# Pipa_PRM.net
KiCad netlist of a schematic drawn in Altium Designer
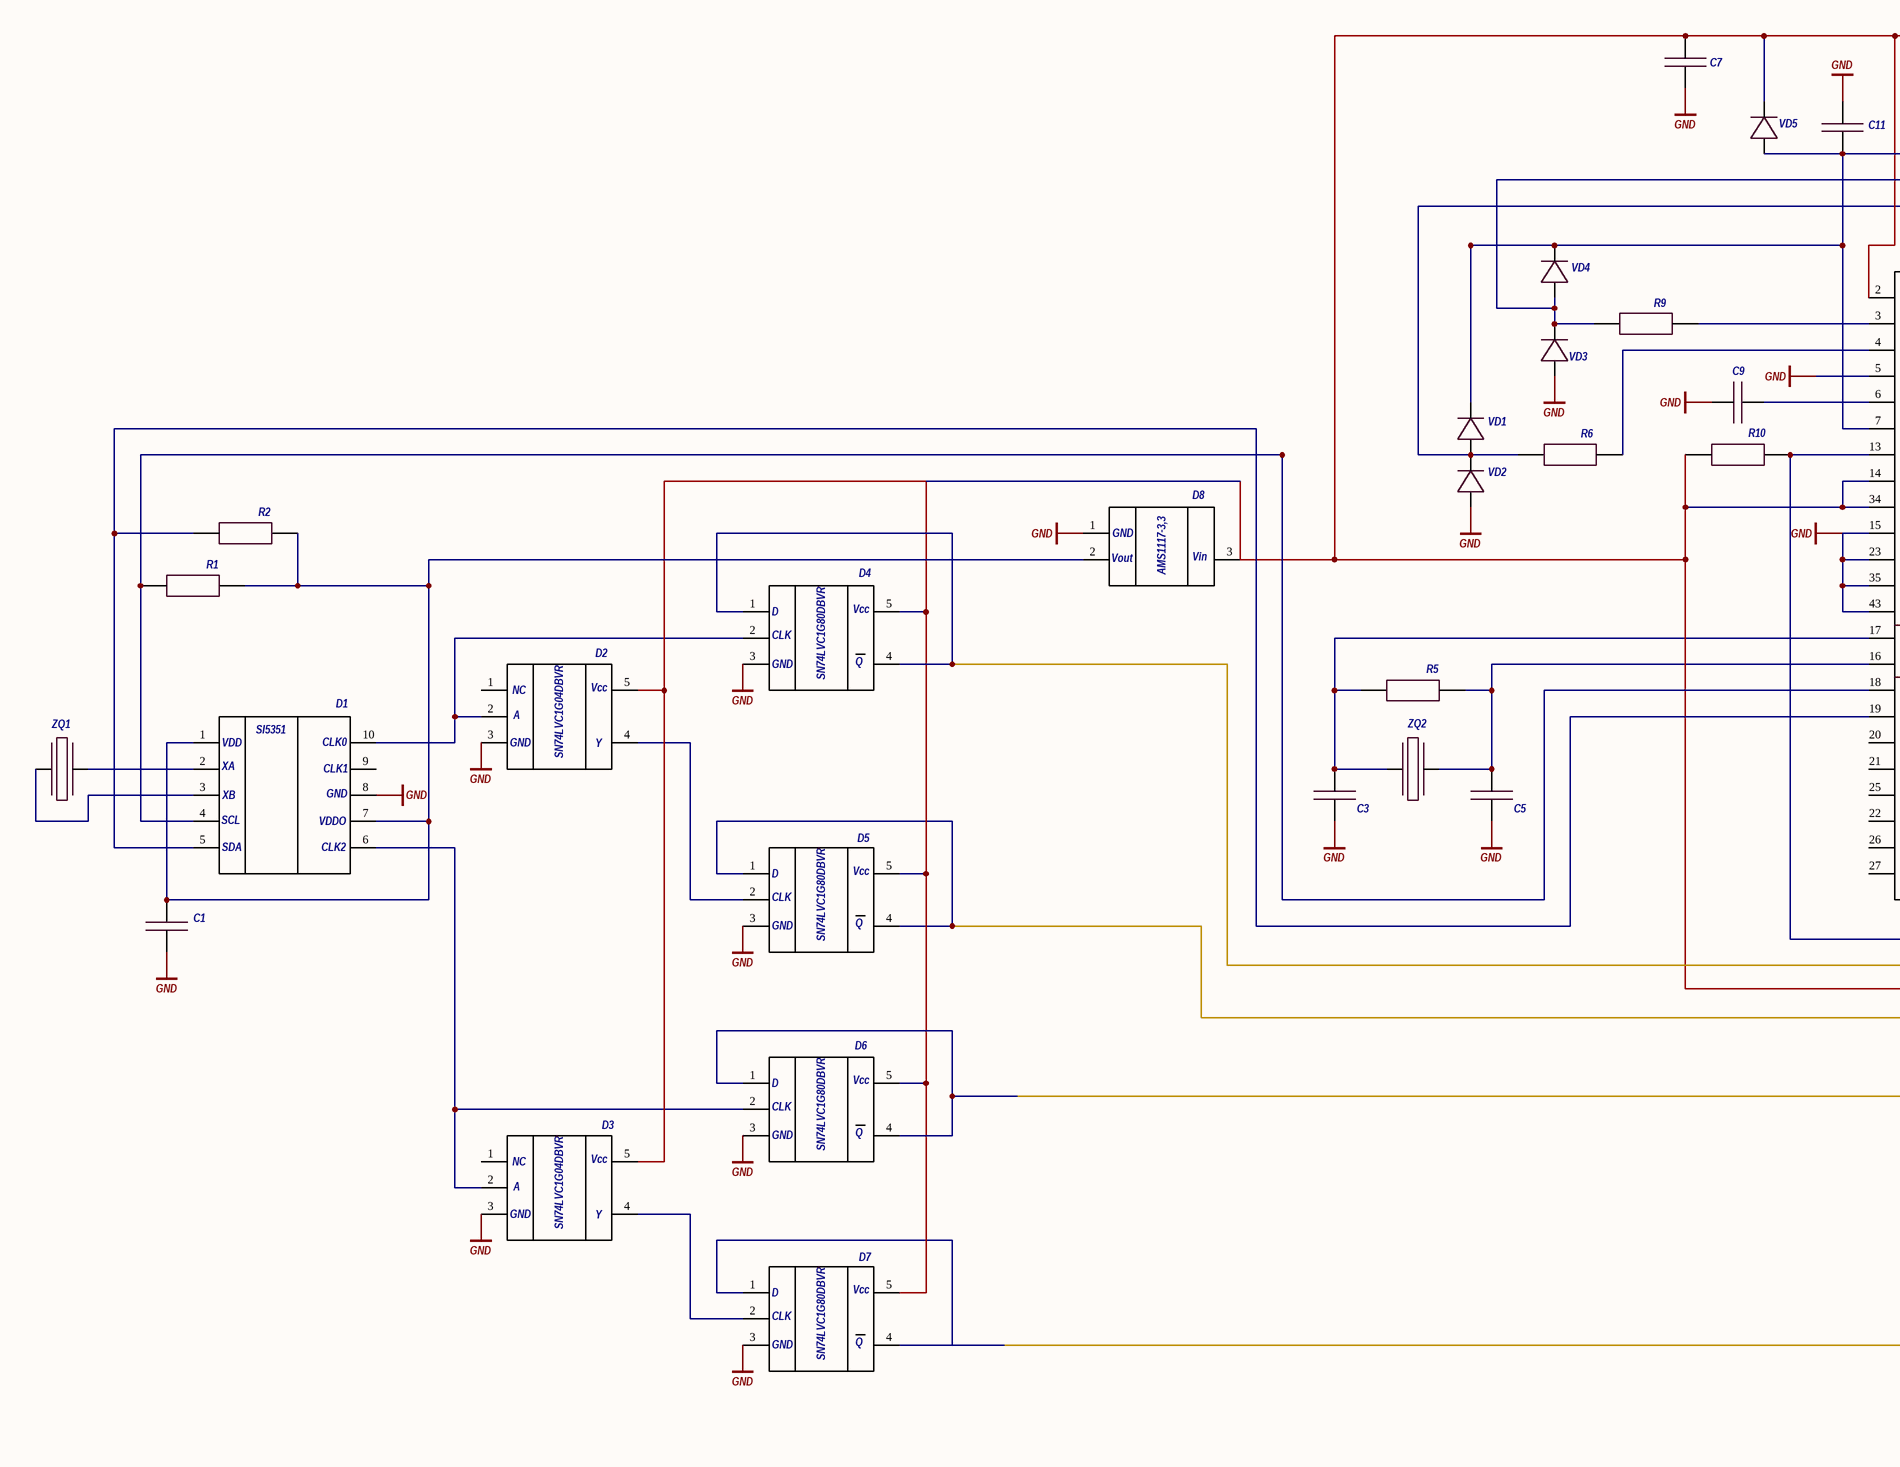
[diagram p0: Pipa PRM.SchDoc, top left]
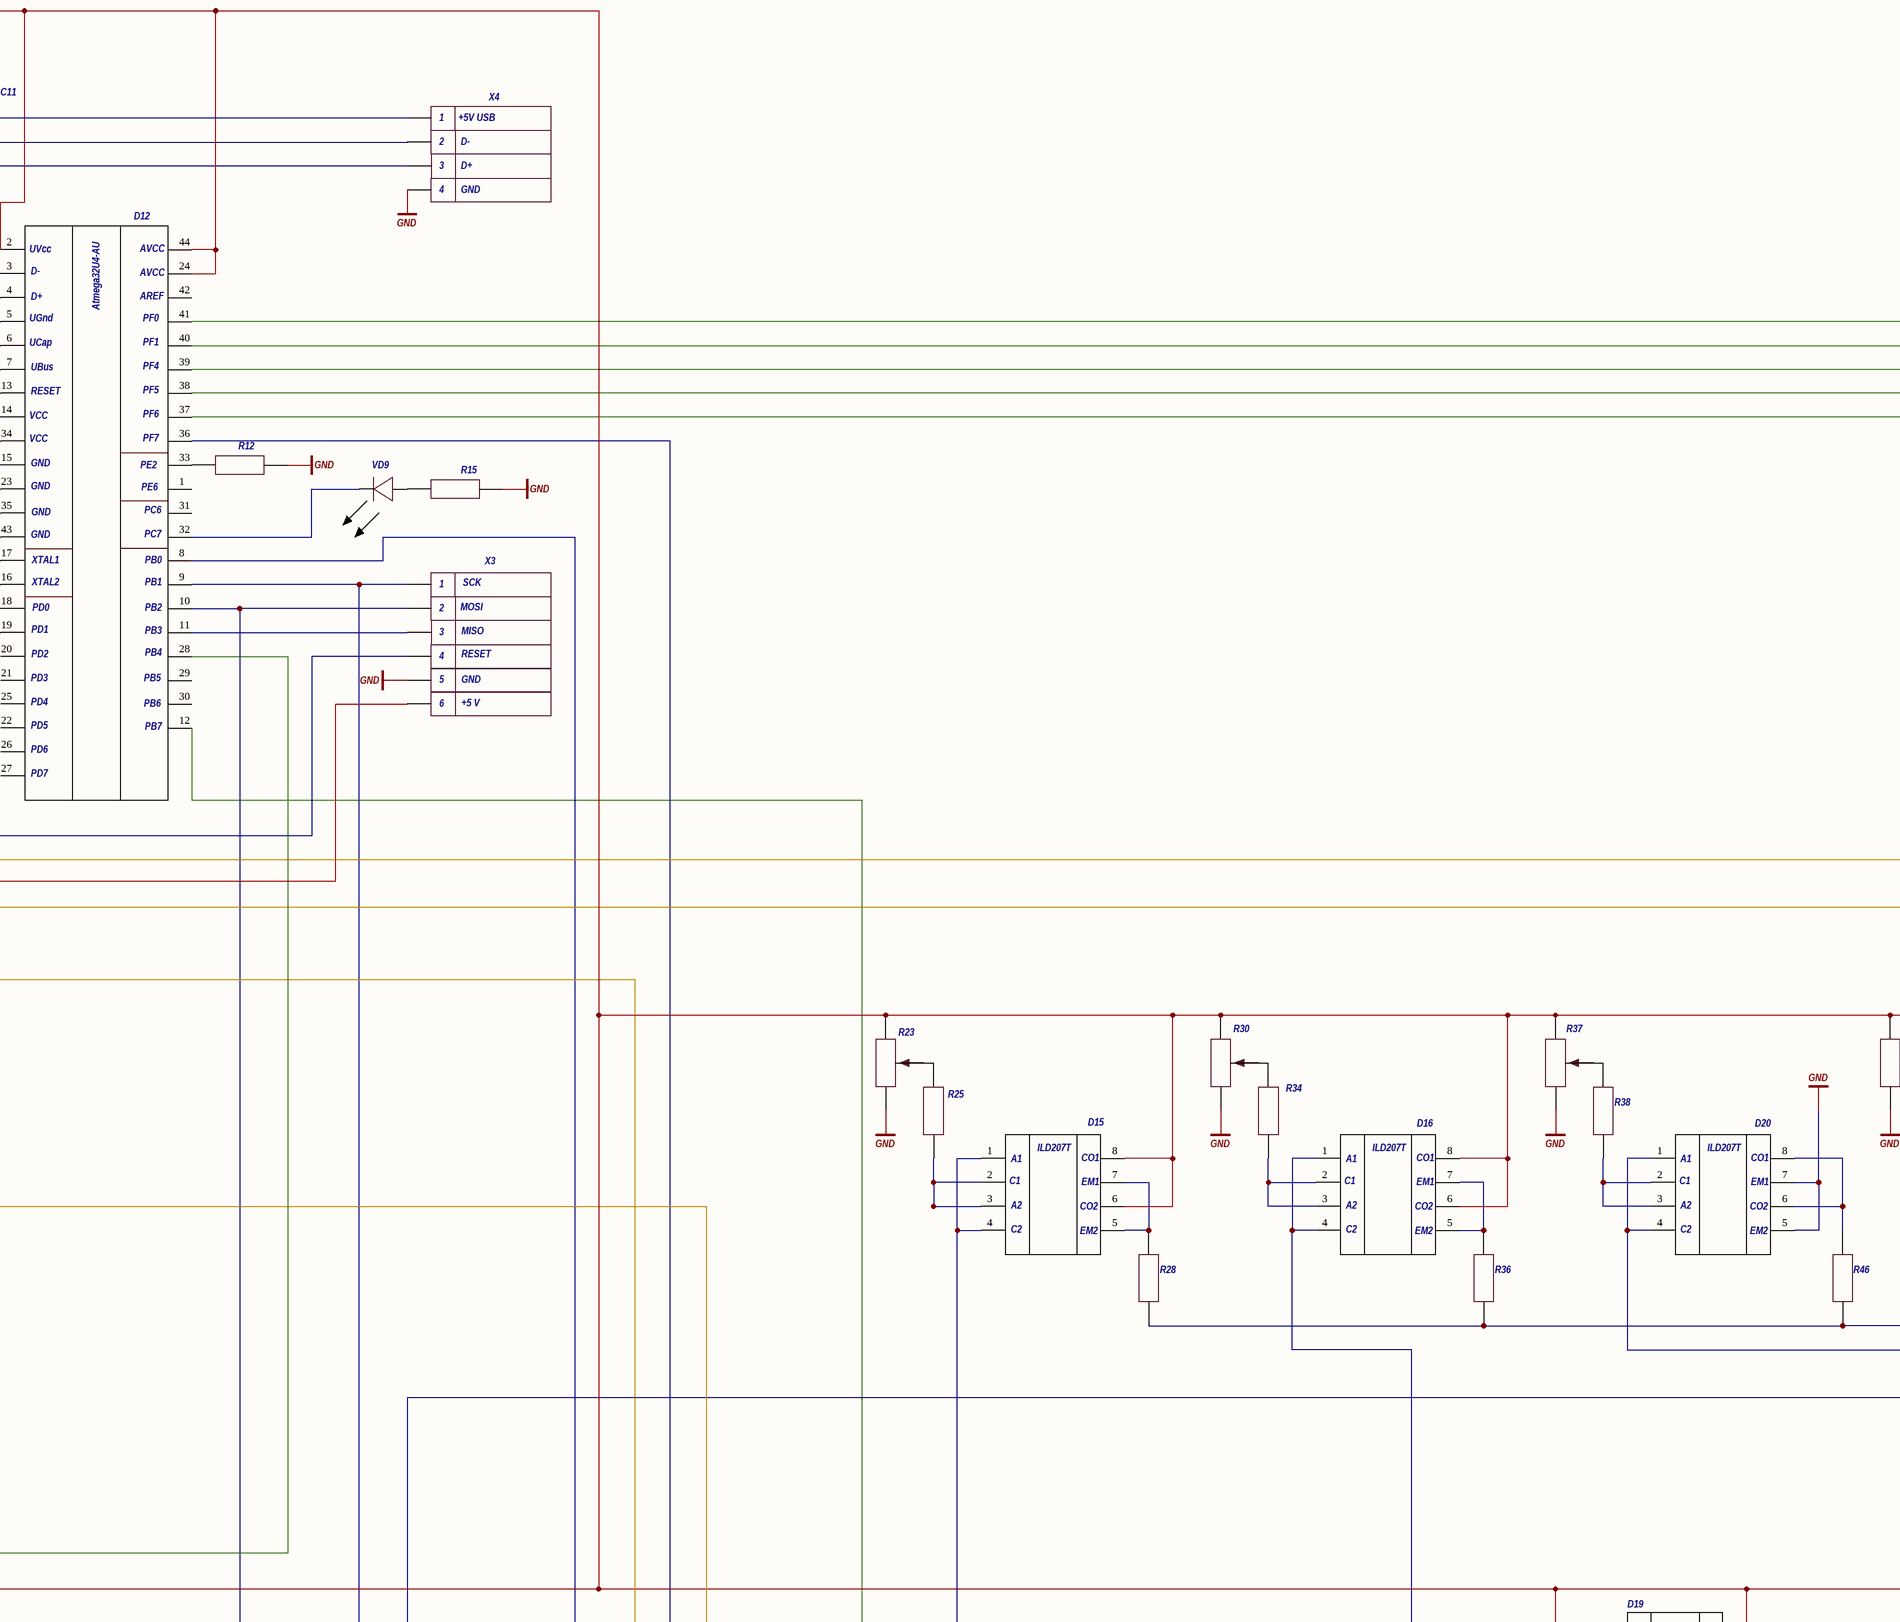
[diagram p1: Pipa PRM.SchDoc, top middle]
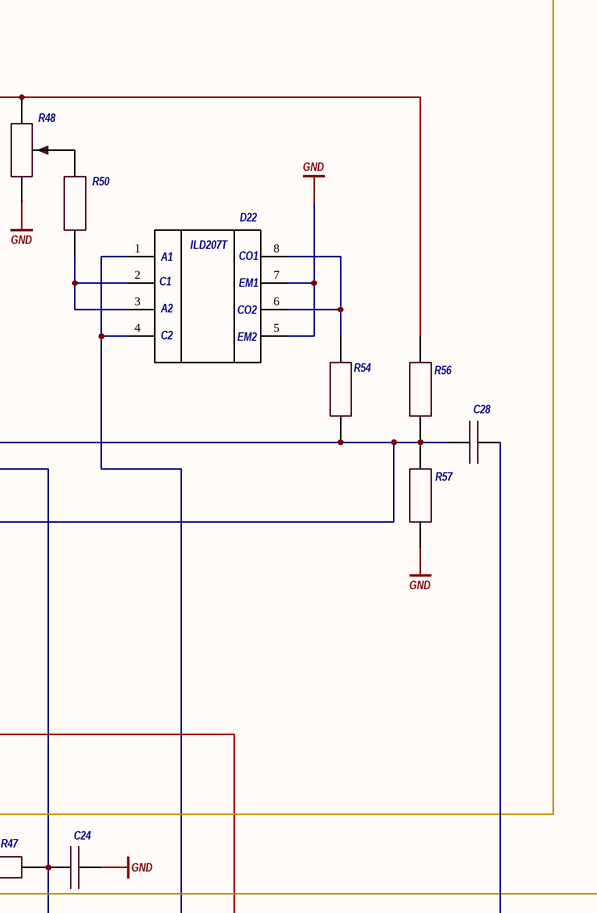
[diagram p2: Pipa PRM.SchDoc, top right]
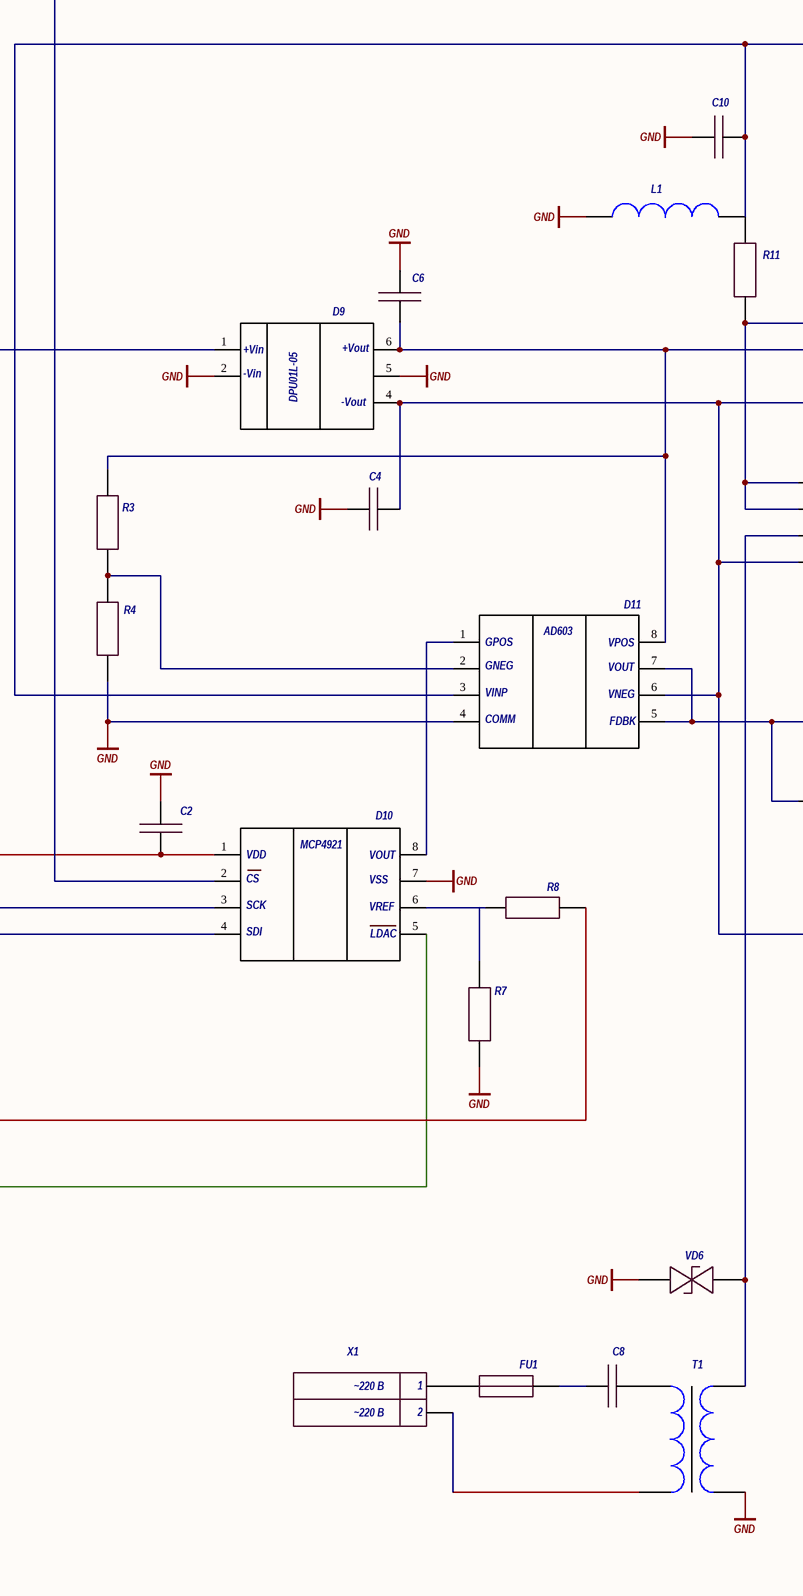
[diagram p3: Pipa PRM.SchDoc, bottom left]
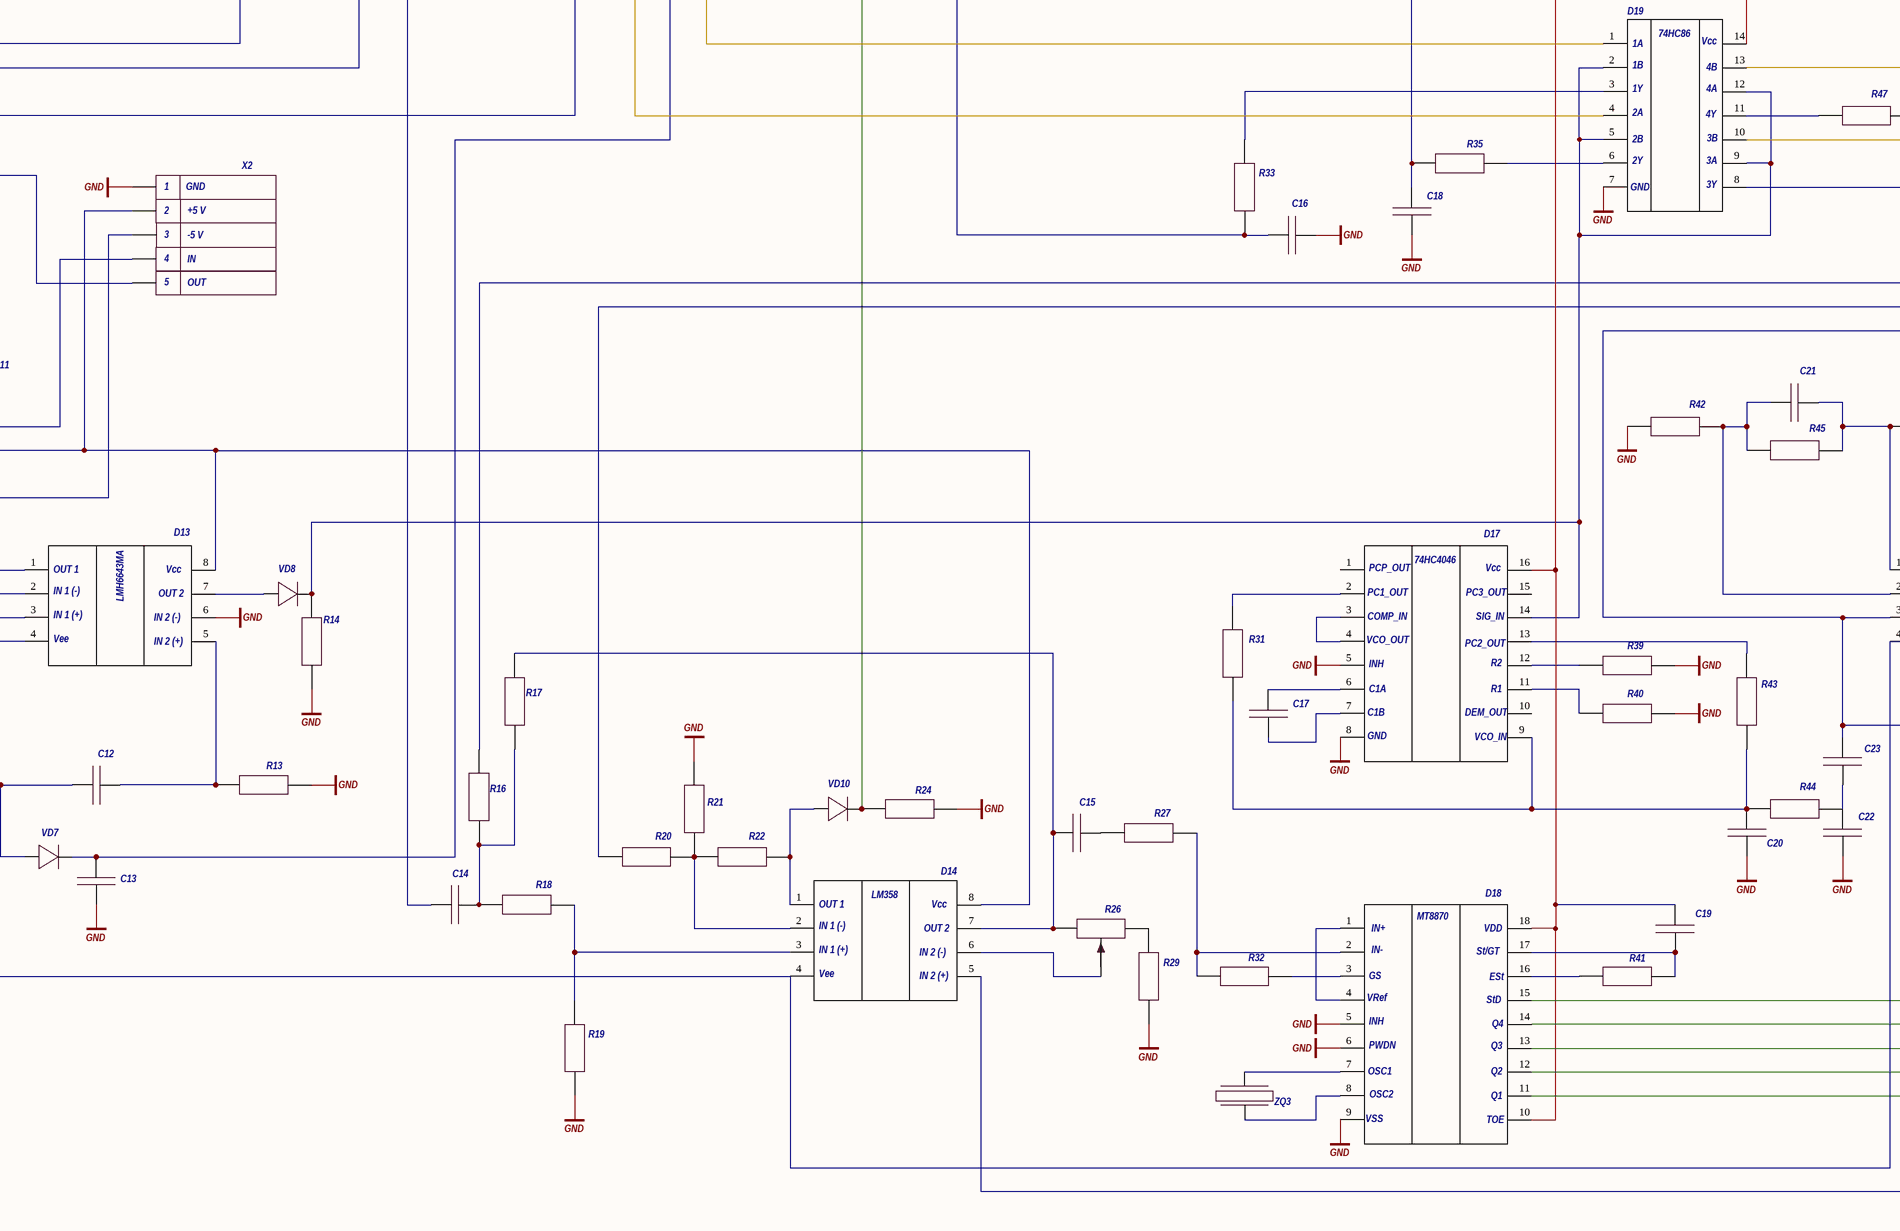
[diagram p4: Pipa PRM.SchDoc, bottom middle]
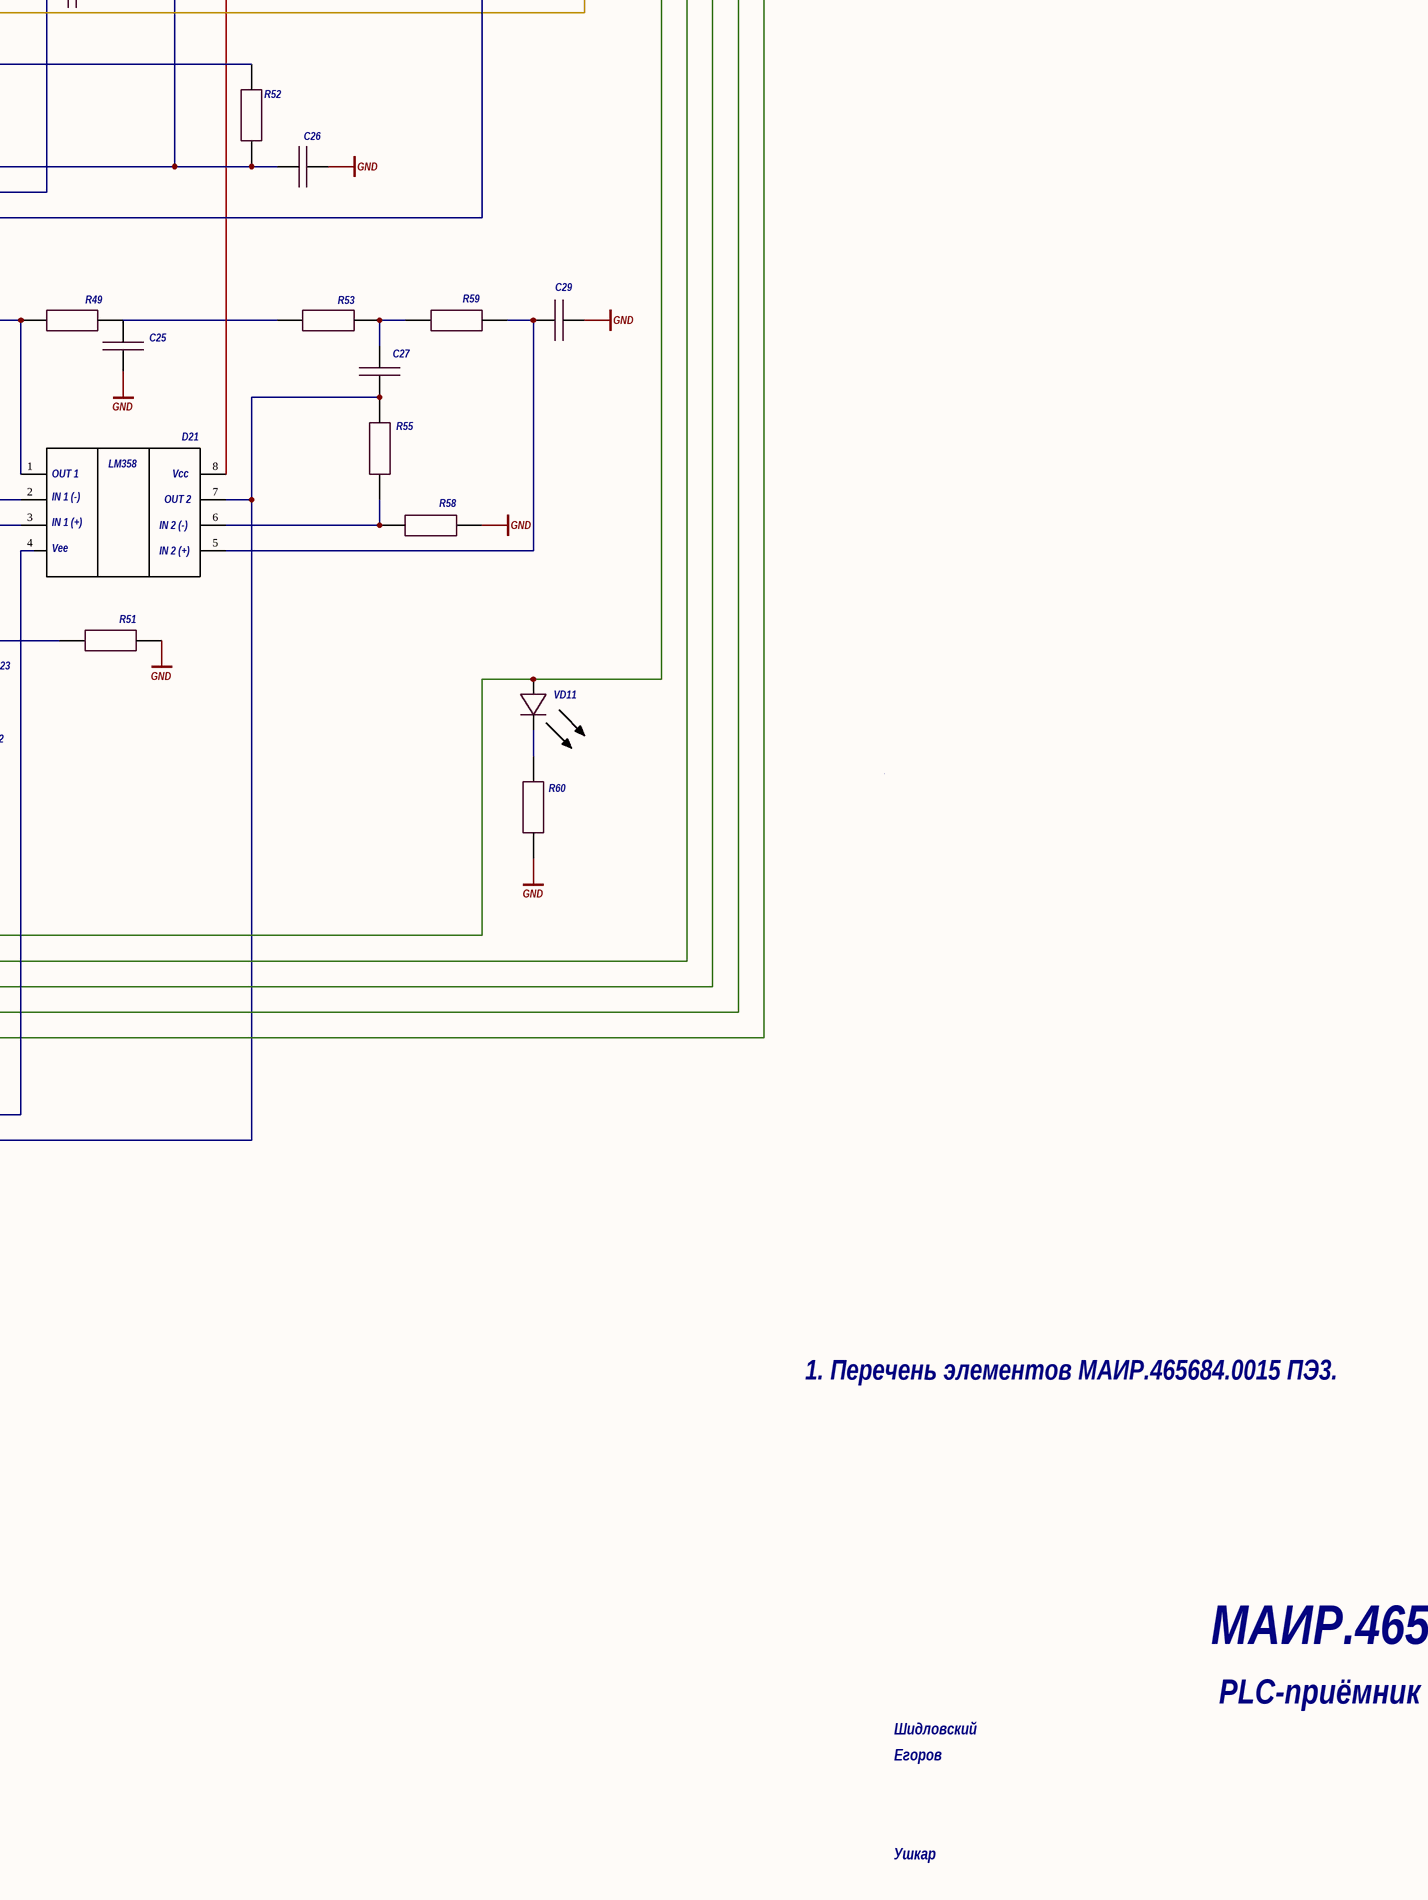
[diagram p5: Pipa PRM.SchDoc, bottom right]

(export (version "E")
  (design (tool "Eeschema 10.0.6"))
  (components
    (comp (ref "C1")
      (value "22 мкФ")
      (footprint "Chokochillipcb:С_0805")
      (libsource (lib "diplom_schlib") (part "Конденсатор"))
    )
    (comp (ref "C2") (value "4,7 мкФ") (libsource (lib "Chokochillisch") (part "Конденсатор")))
    (comp (ref "C3") (value "24 пФ") (libsource (lib "Chokochillisch") (part "Конденсатор")))
    (comp (ref "C4") (value "22 мкФ") (libsource (lib "Chokochillisch") (part "Конденсатор")))
    (comp (ref "C5") (value "24 пФ") (libsource (lib "Chokochillisch") (part "Конденсатор")))
    (comp (ref "C6") (value "22 мкФ") (libsource (lib "Chokochillisch") (part "Конденсатор")))
    (comp (ref "C7")
      (value "470 мкФ 6,3 В Электролит.")
      (libsource (lib "Chokochillisch") (part "Конденсатор"))
    )
    (comp (ref "C8")
      (value "Конденсатор")
      (footprint "Chokochillipcb:С_0805")
      (libsource (lib "diplom_schlib") (part "Конденсатор"))
    )
    (comp (ref "C9") (value "1 мкФ") (libsource (lib "Chokochillisch") (part "Конденсатор")))
    (comp (ref "C10") (value "Конденсатор") (libsource (lib "Chokochillisch") (part "Конденсатор")))
    (comp (ref "C11") (value "10 мкФ") (libsource (lib "Chokochillisch") (part "Конденсатор")))
    (comp (ref "C12") (value "10 мкФ") (libsource (lib "Chokochillisch") (part "Конденсатор")))
    (comp (ref "C13") (value "1 мкФ") (libsource (lib "Chokochillisch") (part "Конденсатор")))
    (comp (ref "C14") (value "22 мкФ") (libsource (lib "Chokochillisch") (part "Конденсатор")))
    (comp (ref "C15")
      (value "1 мкФ")
      (footprint "Chokochillipcb:С_0805")
      (libsource (lib "diplom_schlib") (part "Конденсатор"))
    )
    (comp (ref "C16") (value "100 мкФ (1206)") (libsource (lib "Chokochillisch") (part "Конденсатор")))
    (comp (ref "C17")
      (value "Конденсатор")
      (footprint "Chokochillipcb:С_0805")
      (libsource (lib "diplom_schlib") (part "Конденсатор"))
    )
    (comp (ref "C18") (value "100 мкФ (1206)") (libsource (lib "Chokochillisch") (part "Конденсатор")))
    (comp (ref "C19")
      (value "0,01 мкФ")
      (footprint "Chokochillipcb:С_0805")
      (libsource (lib "diplom_schlib") (part "Конденсатор"))
    )
    (comp (ref "C20")
      (value "Конденсатор")
      (footprint "Chokochillipcb:C_1206")
      (libsource (lib "diplom_schlib") (part "Конденсатор"))
    )
    (comp (ref "C21")
      (value "Конденсатор")
      (footprint "Chokochillipcb:С_0805")
      (libsource (lib "diplom_schlib") (part "Конденсатор"))
    )
    (comp (ref "C22")
      (value "Конденсатор")
      (footprint "Chokochillipcb:С_0805")
      (libsource (lib "diplom_schlib") (part "Конденсатор"))
    )
    (comp (ref "C23") (value "22 мкФ") (libsource (lib "Chokochillisch") (part "Конденсатор")))
    (comp (ref "C24") (value "100 мкФ (1206)") (libsource (lib "Chokochillisch") (part "Конденсатор")))
    (comp (ref "C25") (value "4,3 нФ") (libsource (lib "Chokochillisch") (part "Конденсатор")))
    (comp (ref "C26") (value "100 мкФ (1206)") (libsource (lib "Chokochillisch") (part "Конденсатор")))
    (comp (ref "C27") (value "11 нФ") (libsource (lib "Chokochillisch") (part "Конденсатор")))
    (comp (ref "C28") (value "22 мкФ") (libsource (lib "Chokochillisch") (part "Конденсатор")))
    (comp (ref "C29") (value "620 пФ") (libsource (lib "Chokochillisch") (part "Конденсатор")))
    (comp (ref "D1")
      (value "Микросхема SI5351")
      (footprint "Chokochillipcb:MSOP-10")
      (libsource (lib "diplom_schlib") (part "Микросхема SI5351"))
    )
    (comp (ref "D2")
      (value "Микросхема SN74LVC1G04DBVR")
      (libsource (lib "Chokochillisch") (part "Микросхема SN74LVC1G04DBVR"))
    )
    (comp (ref "D3")
      (value "Микросхема SN74LVC1G04DBVR")
      (libsource (lib "Chokochillisch") (part "Микросхема SN74LVC1G04DBVR"))
    )
    (comp (ref "D4")
      (value "Микросхема SN74LVC1G80DBVR")
      (libsource (lib "Chokochillisch") (part "Микросхема SN74LVC1G80DBVR"))
    )
    (comp (ref "D5")
      (value "Микросхема SN74LVC1G80DBVR")
      (libsource (lib "Chokochillisch") (part "Микросхема SN74LVC1G80DBVR"))
    )
    (comp (ref "D6")
      (value "Микросхема SN74LVC1G80DBVR")
      (libsource (lib "Chokochillisch") (part "Микросхема SN74LVC1G80DBVR"))
    )
    (comp (ref "D7")
      (value "Микросхема SN74LVC1G80DBVR")
      (libsource (lib "Chokochillisch") (part "Микросхема SN74LVC1G80DBVR"))
    )
    (comp (ref "D8")
      (value "Микросхема AMS1117-3,3")
      (footprint "Chokochillipcb:SOT-223")
      (libsource (lib "diplom_schlib") (part "Микросхема AMS1117-3,3"))
    )
    (comp (ref "D9")
      (value "Микросхема DPU01L-05")
      (libsource (lib "Chokochillisch") (part "Микросхема DPU01L-05"))
    )
    (comp (ref "D10")
      (value "Микросхема MCP4921")
      (libsource (lib "Chokochillisch") (part "Микросхема MCP4921"))
    )
    (comp (ref "D11") (value "Микросхема AD603") (libsource (lib "Chokochillisch") (part "Микросхема AD603")))
    (comp (ref "D12")
      (value "Микросхема ATmega32U4-AU")
      (libsource (lib "Chokochillisch") (part "Микросхема ATmega32U4-AU"))
    )
    (comp (ref "D13")
      (value "Микросхема LMH6643MA")
      (libsource (lib "Chokochillisch") (part "Микросхема LMH6643MA"))
    )
    (comp (ref "D14")
      (value "D")
      (footprint "Chokochillipcb:SOP-8")
      (libsource (lib "diplom_schlib") (part "Микросхема LM358"))
    )
    (comp (ref "D15")
      (value "Микросхема ILD207T")
      (description "Оптопара двойная")
      (libsource (lib "Chokochillisch") (part "Микросхема ILD207T"))
    )
    (comp (ref "D16")
      (value "Микросхема ILD207T")
      (description "Оптопара двойная")
      (libsource (lib "Chokochillisch") (part "Микросхема ILD207T"))
    )
    (comp (ref "D17")
      (value "D")
      (footprint "Chokochillipcb:SO16")
      (libsource (lib "diplom_schlib") (part "Микросхема 74НС4046"))
    )
    (comp (ref "D18")
      (value "D")
      (footprint "Chokochillipcb:DIP18")
      (libsource (lib "diplom_schlib") (part "Микросхема MT8870"))
    )
    (comp (ref "D19")
      (value "Микросхема 74HC86")
      (libsource (lib "Chokochillisch") (part "Микросхема 74HC86"))
    )
    (comp (ref "D20")
      (value "Микросхема ILD207T")
      (description "Оптопара двойная")
      (libsource (lib "Chokochillisch") (part "Микросхема ILD207T"))
    )
    (comp (ref "D21")
      (value "D")
      (footprint "Chokochillipcb:SOP-8")
      (libsource (lib "diplom_schlib") (part "Микросхема LM358"))
    )
    (comp (ref "D22")
      (value "Микросхема ILD207T")
      (description "Оптопара двойная")
      (libsource (lib "Chokochillisch") (part "Микросхема ILD207T"))
    )
    (comp (ref "FU1")
      (value "H520PT")
      (footprint "Chokochillipcb:FU_522.1100")
      (libsource (lib "diplom_schlib") (part "Предохранитель"))
    )
    (comp (ref "L1")
      (value "Катушка индуктивности")
      (libsource (lib "Chokochillisch") (part "Катушка индуктивности"))
    )
    (comp (ref "R1")
      (value "10 кОм")
      (footprint "Chokochillipcb:R_0805")
      (libsource (lib "diplom_schlib") (part "Резистор"))
    )
    (comp (ref "R2")
      (value "10 кОм")
      (footprint "Chokochillipcb:R_0805")
      (libsource (lib "diplom_schlib") (part "Резистор"))
    )
    (comp (ref "R3") (value "18 кОм") (libsource (lib "Chokochillisch") (part "Резистор")))
    (comp (ref "R4") (value "2 кОм") (libsource (lib "Chokochillisch") (part "Резистор")))
    (comp (ref "R5") (value "1 МОм") (libsource (lib "Chokochillisch") (part "Резистор")))
    (comp (ref "R6") (value "22 Ом") (libsource (lib "Chokochillisch") (part "Резистор")))
    (comp (ref "R7") (value "1,2 кОм") (libsource (lib "Chokochillisch") (part "Резистор")))
    (comp (ref "R8") (value "4,7 кОм") (libsource (lib "Chokochillisch") (part "Резистор")))
    (comp (ref "R9") (value "22 Ом") (libsource (lib "Chokochillisch") (part "Резистор")))
    (comp (ref "R10") (value "10 кОм") (libsource (lib "Chokochillisch") (part "Резистор")))
    (comp (ref "R11") (value "Резистор") (libsource (lib "Chokochillisch") (part "Резистор")))
    (comp (ref "R12") (value "10 кОм") (libsource (lib "Chokochillisch") (part "Резистор")))
    (comp (ref "R13") (value "100 кОм") (libsource (lib "Chokochillisch") (part "Резистор")))
    (comp (ref "R14") (value "10 кОм") (libsource (lib "Chokochillisch") (part "Резистор")))
    (comp (ref "R15") (value "1 кОм") (libsource (lib "Chokochillisch") (part "Резистор")))
    (comp (ref "R16") (value "1 МОм") (libsource (lib "Chokochillisch") (part "Резистор")))
    (comp (ref "R17") (value "1 МОм") (libsource (lib "Chokochillisch") (part "Резистор")))
    (comp (ref "R18") (value "0 Ом") (libsource (lib "Chokochillisch") (part "Резистор")))
    (comp (ref "R19") (value "1 МОм") (libsource (lib "Chokochillisch") (part "Резистор")))
    (comp (ref "R20") (value "1 МОм") (libsource (lib "Chokochillisch") (part "Резистор")))
    (comp (ref "R21") (value "0 Ом") (libsource (lib "Chokochillisch") (part "Резистор")))
    (comp (ref "R22") (value "1 МОм") (libsource (lib "Chokochillisch") (part "Резистор")))
    (comp (ref "R23") (value "100 Ом 3362P-1-101LF") (libsource (lib "Chokochillisch") (part "Потенциометр")))
    (comp (ref "R24") (value "10 кОм") (libsource (lib "Chokochillisch") (part "Резистор")))
    (comp (ref "R25") (value "1 кОм") (libsource (lib "Chokochillisch") (part "Резистор")))
    (comp (ref "R26") (value "10 кОм 3362P-1-103LF") (libsource (lib "Chokochillisch") (part "Потенциометр")))
    (comp (ref "R27")
      (value "100 кОм")
      (footprint "Chokochillipcb:R_0805")
      (libsource (lib "diplom_schlib") (part "Резистор"))
    )
    (comp (ref "R28") (value "10 кОм") (libsource (lib "Chokochillisch") (part "Резистор")))
    (comp (ref "R29")
      (value "1 кОМ")
      (footprint "Chokochillipcb:R_0805")
      (libsource (lib "diplom_schlib") (part "Резистор"))
    )
    (comp (ref "R30") (value "100 Ом 3362P-1-101LF") (libsource (lib "Chokochillisch") (part "Потенциометр")))
    (comp (ref "R31")
      (value "Резистор")
      (footprint "Chokochillipcb:R_0805")
      (libsource (lib "diplom_schlib") (part "Резистор"))
    )
    (comp (ref "R32")
      (value "100 кОм")
      (footprint "Chokochillipcb:R_0805")
      (libsource (lib "diplom_schlib") (part "Резистор"))
    )
    (comp (ref "R33") (value "100 Ом") (libsource (lib "Chokochillisch") (part "Резистор")))
    (comp (ref "R34") (value "1 кОм") (libsource (lib "Chokochillisch") (part "Резистор")))
    (comp (ref "R35") (value "100 Ом") (libsource (lib "Chokochillisch") (part "Резистор")))
    (comp (ref "R36") (value "10 кОм") (libsource (lib "Chokochillisch") (part "Резистор")))
    (comp (ref "R37") (value "100 Ом 3362P-1-101LF") (libsource (lib "Chokochillisch") (part "Потенциометр")))
    (comp (ref "R38") (value "1 кОм") (libsource (lib "Chokochillisch") (part "Резистор")))
    (comp (ref "R39")
      (value "Резистор")
      (footprint "Chokochillipcb:R_0805")
      (libsource (lib "diplom_schlib") (part "Резистор"))
    )
    (comp (ref "R40")
      (value "Резистор")
      (footprint "Chokochillipcb:R_0805")
      (libsource (lib "diplom_schlib") (part "Резистор"))
    )
    (comp (ref "R41")
      (value "10 кОм")
      (footprint "Chokochillipcb:R_0805")
      (libsource (lib "diplom_schlib") (part "Резистор"))
    )
    (comp (ref "R42")
      (value "Резистор")
      (footprint "Chokochillipcb:R_0805")
      (libsource (lib "diplom_schlib") (part "Резистор"))
    )
    (comp (ref "R43")
      (value "Резистор")
      (footprint "Chokochillipcb:R_0805")
      (libsource (lib "diplom_schlib") (part "Резистор"))
    )
    (comp (ref "R44")
      (value "Резистор")
      (footprint "Chokochillipcb:R_0805")
      (libsource (lib "diplom_schlib") (part "Резистор"))
    )
    (comp (ref "R45")
      (value "Резистор")
      (footprint "Chokochillipcb:R_0805")
      (libsource (lib "diplom_schlib") (part "Резистор"))
    )
    (comp (ref "R46") (value "10 кОм") (libsource (lib "Chokochillisch") (part "Резистор")))
    (comp (ref "R47") (value "100 Ом") (libsource (lib "Chokochillisch") (part "Резистор")))
    (comp (ref "R48") (value "100 Ом 3362P-1-101LF") (libsource (lib "Chokochillisch") (part "Потенциометр")))
    (comp (ref "R49") (value "10 кОм") (libsource (lib "Chokochillisch") (part "Резистор")))
    (comp (ref "R50") (value "1 кОм") (libsource (lib "Chokochillisch") (part "Резистор")))
    (comp (ref "R51") (value "100 кОм") (libsource (lib "Chokochillisch") (part "Резистор")))
    (comp (ref "R52") (value "100 Ом") (libsource (lib "Chokochillisch") (part "Резистор")))
    (comp (ref "R53") (value "10 кОм") (libsource (lib "Chokochillisch") (part "Резистор")))
    (comp (ref "R54") (value "10кОм") (libsource (lib "Chokochillisch") (part "Резистор")))
    (comp (ref "R55") (value "0 Ом") (libsource (lib "Chokochillisch") (part "Резистор")))
    (comp (ref "R56") (value "10 кОм") (libsource (lib "Chokochillisch") (part "Резистор")))
    (comp (ref "R57") (value "10 кОм") (libsource (lib "Chokochillisch") (part "Резистор")))
    (comp (ref "R58") (value "1 МОм") (libsource (lib "Chokochillisch") (part "Резистор")))
    (comp (ref "R59") (value "10 кОм") (libsource (lib "Chokochillisch") (part "Резистор")))
    (comp (ref "R60")
      (value "1 кОм")
      (footprint "Chokochillipcb:R_0805")
      (libsource (lib "diplom_schlib") (part "Резистор"))
    )
    (comp (ref "T1")
      (value "PLA10AS3021")
      (footprint "Chokochillipcb:T_PLA10")
      (libsource (lib "diplom_schlib") (part "Трансформатор 4 вывода"))
    )
    (comp (ref "VD1") (value "BAT60AE (SOD-323)") (libsource (lib "Chokochillisch") (part "Диод")))
    (comp (ref "VD2") (value "BAT60AE (SOD-323)") (libsource (lib "Chokochillisch") (part "Диод")))
    (comp (ref "VD3") (value "BAT60AE (SOD-323)") (libsource (lib "Chokochillisch") (part "Диод")))
    (comp (ref "VD4") (value "BAT60AE (SOD-323)") (libsource (lib "Chokochillisch") (part "Диод")))
    (comp (ref "VD5") (value "SS14 (DO-214AC)") (libsource (lib "Chokochillisch") (part "Диод")))
    (comp (ref "VD6")
      (value "PESD5V0 (SOD-323)")
      (libsource (lib "Chokochillisch") (part "Варистор двойной"))
    )
    (comp (ref "VD7") (value "BAT60AE (SOD-323)") (libsource (lib "Chokochillisch") (part "Диод")))
    (comp (ref "VD8") (value "BAT60AE (SOD-323)") (libsource (lib "Chokochillisch") (part "Диод")))
    (comp (ref "VD9") (value "Красный (0805)") (libsource (lib "Chokochillisch") (part "Светодиод")))
    (comp (ref "VD10") (value "BAT60AE (SOD-323)") (libsource (lib "Chokochillisch") (part "Диод")))
    (comp (ref "VD11")
      (value "Белый (0805)")
      (footprint "Chokochillipcb:VD_0603 SMD LED")
      (libsource (lib "diplom_schlib") (part "Светодиод"))
    )
    (comp (ref "X1")
      (value "Разъём 2 пин")
      (footprint "Chokochillipcb:X_GT950-9.5-02P-14-00")
      (libsource (lib "diplom_schlib") (part "Разъём 2 пин"))
    )
    (comp (ref "X2") (value "PBS-5") (libsource (lib "Chokochillisch") (part "Разъём 5 пин")))
    (comp (ref "X3") (value "PLS-6") (libsource (lib "Chokochillisch") (part "Разъём 6 пин")))
    (comp (ref "X4") (value "USB-B") (libsource (lib "Chokochillisch") (part "Разъём 4 пин")))
    (comp (ref "ZQ1")
      (value "25 МГц в отв.")
      (footprint "Chokochillipcb:ZQ_SJK-6C-25.000-16- 50-30-F-C-50-HJ")
      (libsource (lib "diplom_schlib") (part "Резонатор"))
    )
    (comp (ref "ZQ2") (value "16 МГц в отв.") (libsource (lib "Chokochillisch") (part "Резонатор")))
    (comp (ref "ZQ3")
      (value "3,579545 МГц в отв.")
      (footprint "Chokochillipcb:HC-49U")
      (libsource (lib "diplom_schlib") (part "Резонатор"))
    )
  )
  (nets
    (net (code "1") (name "GND") (class "Default")
      (node (ref "C1") (pin "2") (pinfunction "2_2") (pintype "passive"))
      (node (ref "C10") (pin "1") (pinfunction "1_1") (pintype "passive"))
      (node (ref "C11") (pin "2") (pinfunction "2_2") (pintype "passive"))
      (node (ref "C13") (pin "1") (pinfunction "1_1") (pintype "passive"))
      (node (ref "C16") (pin "1") (pinfunction "1_1") (pintype "passive"))
      (node (ref "C18") (pin "1") (pinfunction "1_1") (pintype "passive"))
      (node (ref "C2") (pin "2") (pinfunction "2_2") (pintype "passive"))
      (node (ref "C20") (pin "2") (pinfunction "2_2") (pintype "passive"))
      (node (ref "C22") (pin "2") (pinfunction "2_2") (pintype "passive"))
      (node (ref "C24") (pin "1") (pinfunction "1_1") (pintype "passive"))
      (node (ref "C25") (pin "1") (pinfunction "1_1") (pintype "passive"))
      (node (ref "C26") (pin "1") (pinfunction "1_1") (pintype "passive"))
      (node (ref "C29") (pin "2") (pinfunction "2_2") (pintype "passive"))
      (node (ref "C3") (pin "1") (pinfunction "1_1") (pintype "passive"))
      (node (ref "C4") (pin "1") (pinfunction "1_1") (pintype "passive"))
      (node (ref "C5") (pin "1") (pinfunction "1_1") (pintype "passive"))
      (node (ref "C6") (pin "2") (pinfunction "2_2") (pintype "passive"))
      (node (ref "C7") (pin "1") (pinfunction "1_1") (pintype "passive"))
      (node (ref "C9") (pin "2") (pinfunction "2_2") (pintype "passive"))
      (node (ref "D1") (pin "8") (pinfunction "8_8") (pintype "passive"))
      (node (ref "D10") (pin "7") (pinfunction "7_7") (pintype "passive"))
      (node (ref "D11") (pin "4") (pinfunction "4_4") (pintype "passive"))
      (node (ref "D12") (pin "15") (pinfunction "15_15") (pintype "passive"))
      (node (ref "D12") (pin "23") (pinfunction "23_23") (pintype "passive"))
      (node (ref "D12") (pin "35") (pinfunction "35_35") (pintype "passive"))
      (node (ref "D12") (pin "43") (pinfunction "43_43") (pintype "passive"))
      (node (ref "D12") (pin "5") (pinfunction "5_5") (pintype "passive"))
      (node (ref "D13") (pin "6") (pinfunction "6_6") (pintype "passive"))
      (node (ref "D17") (pin "5") (pinfunction "5_5") (pintype "passive"))
      (node (ref "D17") (pin "8") (pinfunction "8_8") (pintype "passive"))
      (node (ref "D18") (pin "5") (pinfunction "5_5") (pintype "passive"))
      (node (ref "D18") (pin "6") (pinfunction "6_6") (pintype "passive"))
      (node (ref "D18") (pin "9") (pinfunction "9_9") (pintype "passive"))
      (node (ref "D19") (pin "7") (pinfunction "7_7") (pintype "passive"))
      (node (ref "D2") (pin "3") (pinfunction "3_3") (pintype "passive"))
      (node (ref "D20") (pin "5") (pinfunction "5_5") (pintype "passive"))
      (node (ref "D20") (pin "7") (pinfunction "7_7") (pintype "passive"))
      (node (ref "D22") (pin "5") (pinfunction "5_5") (pintype "passive"))
      (node (ref "D22") (pin "7") (pinfunction "7_7") (pintype "passive"))
      (node (ref "D3") (pin "3") (pinfunction "3_3") (pintype "passive"))
      (node (ref "D4") (pin "3") (pinfunction "3_3") (pintype "passive"))
      (node (ref "D5") (pin "3") (pinfunction "3_3") (pintype "passive"))
      (node (ref "D6") (pin "3") (pinfunction "3_3") (pintype "passive"))
      (node (ref "D7") (pin "3") (pinfunction "3_3") (pintype "passive"))
      (node (ref "D8") (pin "1") (pinfunction "1_1") (pintype "passive"))
      (node (ref "D9") (pin "2") (pinfunction "2_2") (pintype "passive"))
      (node (ref "D9") (pin "5") (pinfunction "5_5") (pintype "passive"))
      (node (ref "L1") (pin "1") (pinfunction "1_1") (pintype "passive"))
      (node (ref "R12") (pin "2") (pinfunction "2_2") (pintype "passive"))
      (node (ref "R13") (pin "2") (pinfunction "2_2") (pintype "passive"))
      (node (ref "R14") (pin "2") (pinfunction "2_2") (pintype "passive"))
      (node (ref "R15") (pin "2") (pinfunction "2_2") (pintype "passive"))
      (node (ref "R19") (pin "1") (pinfunction "1_1") (pintype "passive"))
      (node (ref "R21") (pin "2") (pinfunction "2_2") (pintype "passive"))
      (node (ref "R23") (pin "2") (pinfunction "2_2") (pintype "passive"))
      (node (ref "R24") (pin "2") (pinfunction "2_2") (pintype "passive"))
      (node (ref "R29") (pin "2") (pinfunction "2_2") (pintype "passive"))
      (node (ref "R30") (pin "2") (pinfunction "2_2") (pintype "passive"))
      (node (ref "R37") (pin "2") (pinfunction "2_2") (pintype "passive"))
      (node (ref "R39") (pin "2") (pinfunction "2_2") (pintype "passive"))
      (node (ref "R4") (pin "1") (pinfunction "1_1") (pintype "passive"))
      (node (ref "R40") (pin "2") (pinfunction "2_2") (pintype "passive"))
      (node (ref "R42") (pin "2") (pinfunction "2_2") (pintype "passive"))
      (node (ref "R48") (pin "2") (pinfunction "2_2") (pintype "passive"))
      (node (ref "R51") (pin "2") (pinfunction "2_2") (pintype "passive"))
      (node (ref "R57") (pin "2") (pinfunction "2_2") (pintype "passive"))
      (node (ref "R58") (pin "1") (pinfunction "1_1") (pintype "passive"))
      (node (ref "R60") (pin "2") (pinfunction "2_2") (pintype "passive"))
      (node (ref "R7") (pin "1") (pinfunction "1_1") (pintype "passive"))
      (node (ref "T1") (pin "3") (pinfunction "3_3") (pintype "passive"))
      (node (ref "VD2") (pin "1") (pinfunction "1_1") (pintype "passive"))
      (node (ref "VD3") (pin "1") (pinfunction "1_1") (pintype "passive"))
      (node (ref "VD6") (pin "1") (pinfunction "1_1") (pintype "passive"))
      (node (ref "X2") (pin "1") (pinfunction "1_1") (pintype "passive"))
      (node (ref "X3") (pin "5") (pinfunction "5_5") (pintype "passive"))
      (node (ref "X4") (pin "4") (pinfunction "4_4") (pintype "passive"))
    )
    (net (code "2") (name "Net-(C1-Pad1)") (class "Default")
      (node (ref "C1") (pin "1") (pinfunction "1_1") (pintype "passive"))
      (node (ref "D1") (pin "1") (pinfunction "1_1") (pintype "passive"))
      (node (ref "D1") (pin "7") (pinfunction "7_7") (pintype "passive"))
      (node (ref "D8") (pin "2") (pinfunction "2_2") (pintype "passive"))
      (node (ref "R1") (pin "1") (pinfunction "1_1") (pintype "passive"))
      (node (ref "R2") (pin "1") (pinfunction "1_1") (pintype "passive"))
    )
    (net (code "3") (name "Net-(C3-Pad2)") (class "Default")
      (node (ref "C3") (pin "2") (pinfunction "2_2") (pintype "passive"))
      (node (ref "D12") (pin "17") (pinfunction "17_17") (pintype "passive"))
      (node (ref "R5") (pin "1") (pinfunction "1_1") (pintype "passive"))
      (node (ref "ZQ2") (pin "1") (pinfunction "1_1") (pintype "passive"))
    )
    (net (code "4") (name "Net-(C4-Pad2)") (class "Default")
      (node (ref "C4") (pin "2") (pinfunction "2_2") (pintype "passive"))
      (node (ref "D11") (pin "6") (pinfunction "6_6") (pintype "passive"))
      (node (ref "D13") (pin "4") (pinfunction "4_4") (pintype "passive"))
      (node (ref "D14") (pin "4") (pinfunction "4_4") (pintype "passive"))
      (node (ref "D21") (pin "4") (pinfunction "4_4") (pintype "passive"))
      (node (ref "D9") (pin "4") (pinfunction "4_4") (pintype "passive"))
      (node (ref "X2") (pin "3") (pinfunction "3_3") (pintype "passive"))
    )
    (net (code "5") (name "Net-(C5-Pad2)") (class "Default")
      (node (ref "C5") (pin "2") (pinfunction "2_2") (pintype "passive"))
      (node (ref "D12") (pin "16") (pinfunction "16_16") (pintype "passive"))
      (node (ref "R5") (pin "2") (pinfunction "2_2") (pintype "passive"))
      (node (ref "ZQ2") (pin "2") (pinfunction "2_2") (pintype "passive"))
    )
    (net (code "6") (name "Net-(C6-Pad1)") (class "Default")
      (node (ref "C6") (pin "1") (pinfunction "1_1") (pintype "passive"))
      (node (ref "D11") (pin "8") (pinfunction "8_8") (pintype "passive"))
      (node (ref "D13") (pin "8") (pinfunction "8_8") (pintype "passive"))
      (node (ref "D14") (pin "8") (pinfunction "8_8") (pintype "passive"))
      (node (ref "D9") (pin "6") (pinfunction "6_6") (pintype "passive"))
      (node (ref "R3") (pin "2") (pinfunction "2_2") (pintype "passive"))
      (node (ref "X2") (pin "2") (pinfunction "2_2") (pintype "passive"))
    )
    (net (code "7") (name "Net-(C8-Pad1)") (class "Default")
      (node (ref "C8") (pin "1") (pinfunction "1_1") (pintype "passive"))
      (node (ref "FU1") (pin "2") (pinfunction "2_2") (pintype "passive"))
    )
    (net (code "8") (name "Net-(C8-Pad2)") (class "Default")
      (node (ref "C8") (pin "2") (pinfunction "2_2") (pintype "passive"))
      (node (ref "T1") (pin "1") (pinfunction "1_1") (pintype "passive"))
    )
    (net (code "9") (name "Net-(C9-Pad1)") (class "Default")
      (node (ref "C9") (pin "1") (pinfunction "1_1") (pintype "passive"))
      (node (ref "D12") (pin "6") (pinfunction "6_6") (pintype "passive"))
    )
    (net (code "10") (name "Net-(C10-Pad2)") (class "Default")
      (node (ref "C10") (pin "2") (pinfunction "2_2") (pintype "passive"))
      (node (ref "D11") (pin "3") (pinfunction "3_3") (pintype "passive"))
      (node (ref "L1") (pin "2") (pinfunction "2_2") (pintype "passive"))
      (node (ref "R11") (pin "1") (pinfunction "1_1") (pintype "passive"))
      (node (ref "X2") (pin "5") (pinfunction "5_5") (pintype "passive"))
    )
    (net (code "11") (name "Net-(C11-Pad1)") (class "Default")
      (node (ref "C11") (pin "1") (pinfunction "1_1") (pintype "passive"))
      (node (ref "D12") (pin "7") (pinfunction "7_7") (pintype "passive"))
      (node (ref "VD1") (pin "2") (pinfunction "2_2") (pintype "passive"))
      (node (ref "VD4") (pin "2") (pinfunction "2_2") (pintype "passive"))
      (node (ref "VD5") (pin "1") (pinfunction "1_1") (pintype "passive"))
      (node (ref "X4") (pin "1") (pinfunction "1_1") (pintype "passive"))
    )
    (net (code "12") (name "Net-(C12-Pad1)") (class "Default")
      (node (ref "C12") (pin "1") (pinfunction "1_1") (pintype "passive"))
      (node (ref "D11") (pin "5") (pinfunction "5_5") (pintype "passive"))
      (node (ref "D11") (pin "7") (pinfunction "7_7") (pintype "passive"))
      (node (ref "VD7") (pin "1") (pinfunction "1_1") (pintype "passive"))
    )
    (net (code "13") (name "Net-(C12-Pad2)") (class "Default")
      (node (ref "C12") (pin "2") (pinfunction "2_2") (pintype "passive"))
      (node (ref "D13") (pin "5") (pinfunction "5_5") (pintype "passive"))
      (node (ref "R13") (pin "1") (pinfunction "1_1") (pintype "passive"))
    )
    (net (code "14") (name "Net-(C13-Pad2)") (class "Default")
      (node (ref "C13") (pin "2") (pinfunction "2_2") (pintype "passive"))
      (node (ref "D12") (pin "36") (pinfunction "36_36") (pintype "passive"))
      (node (ref "VD7") (pin "2") (pinfunction "2_2") (pintype "passive"))
    )
    (net (code "15") (name "Net-(C14-Pad1)") (class "Default")
      (node (ref "C14") (pin "1") (pinfunction "1_1") (pintype "passive"))
      (node (ref "R16") (pin "1") (pinfunction "1_1") (pintype "passive"))
      (node (ref "R17") (pin "1") (pinfunction "1_1") (pintype "passive"))
      (node (ref "R18") (pin "1") (pinfunction "1_1") (pintype "passive"))
    )
    (net (code "16") (name "Net-(C14-Pad2)") (class "Default")
      (node (ref "C14") (pin "2") (pinfunction "2_2") (pintype "passive"))
      (node (ref "C28") (pin "2") (pinfunction "2_2") (pintype "passive"))
      (node (ref "R28") (pin "1") (pinfunction "1_1") (pintype "passive"))
      (node (ref "R36") (pin "1") (pinfunction "1_1") (pintype "passive"))
      (node (ref "R46") (pin "2") (pinfunction "2_2") (pintype "passive"))
      (node (ref "R54") (pin "2") (pinfunction "2_2") (pintype "passive"))
      (node (ref "R56") (pin "2") (pinfunction "2_2") (pintype "passive"))
      (node (ref "R57") (pin "1") (pinfunction "1_1") (pintype "passive"))
    )
    (net (code "17") (name "Net-(C15-Pad1)") (class "Default")
      (node (ref "C15") (pin "1") (pinfunction "1_1") (pintype "passive"))
      (node (ref "R27") (pin "2") (pinfunction "2_2") (pintype "passive"))
    )
    (net (code "18") (name "Net-(C15-Pad2)") (class "Default")
      (node (ref "C15") (pin "2") (pinfunction "2_2") (pintype "passive"))
      (node (ref "D14") (pin "7") (pinfunction "7_7") (pintype "passive"))
      (node (ref "R17") (pin "2") (pinfunction "2_2") (pintype "passive"))
      (node (ref "R26") (pin "2") (pinfunction "2_2") (pintype "passive"))
    )
    (net (code "19") (name "Net-(C16-Pad2)") (class "Default")
      (node (ref "C16") (pin "2") (pinfunction "2_2") (pintype "passive"))
      (node (ref "D15") (pin "1") (pinfunction "1_1") (pintype "passive"))
      (node (ref "D15") (pin "4") (pinfunction "4_4") (pintype "passive"))
      (node (ref "R33") (pin "1") (pinfunction "1_1") (pintype "passive"))
    )
    (net (code "20") (name "Net-(C17-Pad1)") (class "Default")
      (node (ref "C17") (pin "1") (pinfunction "1_1") (pintype "passive"))
      (node (ref "D17") (pin "7") (pinfunction "7_7") (pintype "passive"))
    )
    (net (code "21") (name "Net-(C17-Pad2)") (class "Default")
      (node (ref "C17") (pin "2") (pinfunction "2_2") (pintype "passive"))
      (node (ref "D17") (pin "6") (pinfunction "6_6") (pintype "passive"))
    )
    (net (code "22") (name "Net-(C18-Pad2)") (class "Default")
      (node (ref "C18") (pin "2") (pinfunction "2_2") (pintype "passive"))
      (node (ref "D16") (pin "1") (pinfunction "1_1") (pintype "passive"))
      (node (ref "D16") (pin "4") (pinfunction "4_4") (pintype "passive"))
      (node (ref "R35") (pin "1") (pinfunction "1_1") (pintype "passive"))
    )
    (net (code "23") (name "Net-(C19-Pad1)") (class "Default")
      (node (ref "C19") (pin "1") (pinfunction "1_1") (pintype "passive"))
      (node (ref "D18") (pin "17") (pinfunction "17_17") (pintype "passive"))
      (node (ref "R41") (pin "2") (pinfunction "2_2") (pintype "passive"))
    )
    (net (code "24") (name "Net-(C19-Pad2)") (class "Default")
      (node (ref "C19") (pin "2") (pinfunction "2_2") (pintype "passive"))
      (node (ref "C2") (pin "1") (pinfunction "1_1") (pintype "passive"))
      (node (ref "C7") (pin "2") (pinfunction "2_2") (pintype "passive"))
      (node (ref "D10") (pin "1") (pinfunction "1_1") (pintype "passive"))
      (node (ref "D12") (pin "14") (pinfunction "14_14") (pintype "passive"))
      (node (ref "D12") (pin "2") (pinfunction "2_2") (pintype "passive"))
      (node (ref "D12") (pin "24") (pinfunction "24_24") (pintype "passive"))
      (node (ref "D12") (pin "34") (pinfunction "34_34") (pintype "passive"))
      (node (ref "D12") (pin "44") (pinfunction "44_44") (pintype "passive"))
      (node (ref "D15") (pin "6") (pinfunction "6_6") (pintype "passive"))
      (node (ref "D15") (pin "8") (pinfunction "8_8") (pintype "passive"))
      (node (ref "D16") (pin "6") (pinfunction "6_6") (pintype "passive"))
      (node (ref "D16") (pin "8") (pinfunction "8_8") (pintype "passive"))
      (node (ref "D17") (pin "16") (pinfunction "16_16") (pintype "passive"))
      (node (ref "D18") (pin "10") (pinfunction "10_10") (pintype "passive"))
      (node (ref "D18") (pin "18") (pinfunction "18_18") (pintype "passive"))
      (node (ref "D19") (pin "14") (pinfunction "14_14") (pintype "passive"))
      (node (ref "D2") (pin "5") (pinfunction "5_5") (pintype "passive"))
      (node (ref "D21") (pin "8") (pinfunction "8_8") (pintype "passive"))
      (node (ref "D3") (pin "5") (pinfunction "5_5") (pintype "passive"))
      (node (ref "D4") (pin "5") (pinfunction "5_5") (pintype "passive"))
      (node (ref "D5") (pin "5") (pinfunction "5_5") (pintype "passive"))
      (node (ref "D6") (pin "5") (pinfunction "5_5") (pintype "passive"))
      (node (ref "D7") (pin "5") (pinfunction "5_5") (pintype "passive"))
      (node (ref "D8") (pin "3") (pinfunction "3_3") (pintype "passive"))
      (node (ref "D9") (pin "1") (pinfunction "1_1") (pintype "passive"))
      (node (ref "R10") (pin "2") (pinfunction "2_2") (pintype "passive"))
      (node (ref "R23") (pin "1") (pinfunction "1_1") (pintype "passive"))
      (node (ref "R30") (pin "1") (pinfunction "1_1") (pintype "passive"))
      (node (ref "R37") (pin "1") (pinfunction "1_1") (pintype "passive"))
      (node (ref "R48") (pin "1") (pinfunction "1_1") (pintype "passive"))
      (node (ref "R56") (pin "1") (pinfunction "1_1") (pintype "passive"))
      (node (ref "R8") (pin "2") (pinfunction "2_2") (pintype "passive"))
      (node (ref "VD5") (pin "2") (pinfunction "2_2") (pintype "passive"))
      (node (ref "X3") (pin "6") (pinfunction "6_6") (pintype "passive"))
    )
    (net (code "25") (name "Net-(C20-Pad1)") (class "Default")
      (node (ref "C20") (pin "1") (pinfunction "1_1") (pintype "passive"))
      (node (ref "D17") (pin "9") (pinfunction "9_9") (pintype "passive"))
      (node (ref "R31") (pin "2") (pinfunction "2_2") (pintype "passive"))
      (node (ref "R43") (pin "1") (pinfunction "1_1") (pintype "passive"))
      (node (ref "R44") (pin "1") (pinfunction "1_1") (pintype "passive"))
    )
    (net (code "26") (name "Net-(C21-Pad1)") (class "Default")
      (node (ref "C21") (pin "1") (pinfunction "1_1") (pintype "passive"))
      (node (ref "D21") (pin "1") (pinfunction "1_1") (pintype "passive"))
      (node (ref "R45") (pin "1") (pinfunction "1_1") (pintype "passive"))
      (node (ref "R49") (pin "1") (pinfunction "1_1") (pintype "passive"))
    )
    (net (code "27") (name "Net-(C21-Pad2)") (class "Default")
      (node (ref "C21") (pin "2") (pinfunction "2_2") (pintype "passive"))
      (node (ref "D21") (pin "2") (pinfunction "2_2") (pintype "passive"))
      (node (ref "R42") (pin "1") (pinfunction "1_1") (pintype "passive"))
      (node (ref "R45") (pin "2") (pinfunction "2_2") (pintype "passive"))
    )
    (net (code "28") (name "Net-(C22-Pad1)") (class "Default")
      (node (ref "C22") (pin "1") (pinfunction "1_1") (pintype "passive"))
      (node (ref "C23") (pin "1") (pinfunction "1_1") (pintype "passive"))
      (node (ref "R44") (pin "2") (pinfunction "2_2") (pintype "passive"))
    )
    (net (code "29") (name "Net-(C23-Pad2)") (class "Default")
      (node (ref "C23") (pin "2") (pinfunction "2_2") (pintype "passive"))
      (node (ref "C28") (pin "1") (pinfunction "1_1") (pintype "passive"))
      (node (ref "D21") (pin "3") (pinfunction "3_3") (pintype "passive"))
      (node (ref "R51") (pin "1") (pinfunction "1_1") (pintype "passive"))
    )
    (net (code "30") (name "Net-(C24-Pad2)") (class "Default")
      (node (ref "C24") (pin "2") (pinfunction "2_2") (pintype "passive"))
      (node (ref "D20") (pin "1") (pinfunction "1_1") (pintype "passive"))
      (node (ref "D20") (pin "4") (pinfunction "4_4") (pintype "passive"))
      (node (ref "R20") (pin "1") (pinfunction "1_1") (pintype "passive"))
      (node (ref "R47") (pin "2") (pinfunction "2_2") (pintype "passive"))
    )
    (net (code "31") (name "Net-(C25-Pad2)") (class "Default")
      (node (ref "C25") (pin "2") (pinfunction "2_2") (pintype "passive"))
      (node (ref "R49") (pin "2") (pinfunction "2_2") (pintype "passive"))
      (node (ref "R53") (pin "1") (pinfunction "1_1") (pintype "passive"))
    )
    (net (code "32") (name "Net-(C26-Pad2)") (class "Default")
      (node (ref "C26") (pin "2") (pinfunction "2_2") (pintype "passive"))
      (node (ref "D22") (pin "1") (pinfunction "1_1") (pintype "passive"))
      (node (ref "D22") (pin "4") (pinfunction "4_4") (pintype "passive"))
      (node (ref "R16") (pin "2") (pinfunction "2_2") (pintype "passive"))
      (node (ref "R52") (pin "1") (pinfunction "1_1") (pintype "passive"))
    )
    (net (code "33") (name "Net-(C27-Pad1)") (class "Default")
      (node (ref "C27") (pin "1") (pinfunction "1_1") (pintype "passive"))
      (node (ref "D14") (pin "5") (pinfunction "5_5") (pintype "passive"))
      (node (ref "D21") (pin "7") (pinfunction "7_7") (pintype "passive"))
      (node (ref "R55") (pin "2") (pinfunction "2_2") (pintype "passive"))
    )
    (net (code "34") (name "Net-(C27-Pad2)") (class "Default")
      (node (ref "C27") (pin "2") (pinfunction "2_2") (pintype "passive"))
      (node (ref "R53") (pin "2") (pinfunction "2_2") (pintype "passive"))
      (node (ref "R59") (pin "1") (pinfunction "1_1") (pintype "passive"))
    )
    (net (code "35") (name "Net-(C29-Pad1)") (class "Default")
      (node (ref "C29") (pin "1") (pinfunction "1_1") (pintype "passive"))
      (node (ref "D21") (pin "5") (pinfunction "5_5") (pintype "passive"))
      (node (ref "R59") (pin "2") (pinfunction "2_2") (pintype "passive"))
    )
    (net (code "36") (name "Net-(D1-Pad2)") (class "Default")
      (node (ref "D1") (pin "2") (pinfunction "2_2") (pintype "passive"))
      (node (ref "ZQ1") (pin "2") (pinfunction "2_2") (pintype "passive"))
    )
    (net (code "37") (name "Net-(D1-Pad3)") (class "Default")
      (node (ref "D1") (pin "3") (pinfunction "3_3") (pintype "passive"))
      (node (ref "ZQ1") (pin "1") (pinfunction "1_1") (pintype "passive"))
    )
    (net (code "38") (name "Net-(D1-Pad4)") (class "Default")
      (node (ref "D1") (pin "4") (pinfunction "4_4") (pintype "passive"))
      (node (ref "D12") (pin "18") (pinfunction "18_18") (pintype "passive"))
      (node (ref "R1") (pin "2") (pinfunction "2_2") (pintype "passive"))
    )
    (net (code "39") (name "Net-(D1-Pad5)") (class "Default")
      (node (ref "D1") (pin "5") (pinfunction "5_5") (pintype "passive"))
      (node (ref "D12") (pin "19") (pinfunction "19_19") (pintype "passive"))
      (node (ref "R2") (pin "2") (pinfunction "2_2") (pintype "passive"))
    )
    (net (code "40") (name "Net-(D1-Pad6)") (class "Default")
      (node (ref "D1") (pin "6") (pinfunction "6_6") (pintype "passive"))
      (node (ref "D3") (pin "2") (pinfunction "2_2") (pintype "passive"))
      (node (ref "D6") (pin "2") (pinfunction "2_2") (pintype "passive"))
    )
    (net (code "41") (name "Net-(D1-Pad10)") (class "Default")
      (node (ref "D1") (pin "10") (pinfunction "10_10") (pintype "passive"))
      (node (ref "D2") (pin "2") (pinfunction "2_2") (pintype "passive"))
      (node (ref "D4") (pin "2") (pinfunction "2_2") (pintype "passive"))
    )
    (net (code "42") (name "Net-(D2-Pad4)") (class "Default")
      (node (ref "D2") (pin "4") (pinfunction "4_4") (pintype "passive"))
      (node (ref "D5") (pin "2") (pinfunction "2_2") (pintype "passive"))
    )
    (net (code "43") (name "Net-(D3-Pad4)") (class "Default")
      (node (ref "D3") (pin "4") (pinfunction "4_4") (pintype "passive"))
      (node (ref "D7") (pin "2") (pinfunction "2_2") (pintype "passive"))
    )
    (net (code "44") (name "Net-(D10-Pad2)") (class "Default")
      (node (ref "D10") (pin "2") (pinfunction "2_2") (pintype "passive"))
      (node (ref "D12") (pin "8") (pinfunction "8_8") (pintype "passive"))
    )
    (net (code "45") (name "Net-(D10-Pad3)") (class "Default")
      (node (ref "D10") (pin "3") (pinfunction "3_3") (pintype "passive"))
      (node (ref "D12") (pin "9") (pinfunction "9_9") (pintype "passive"))
      (node (ref "X3") (pin "1") (pinfunction "1_1") (pintype "passive"))
    )
    (net (code "46") (name "Net-(D10-Pad4)") (class "Default")
      (node (ref "D10") (pin "4") (pinfunction "4_4") (pintype "passive"))
      (node (ref "D12") (pin "10") (pinfunction "10_10") (pintype "passive"))
      (node (ref "X3") (pin "2") (pinfunction "2_2") (pintype "passive"))
    )
    (net (code "47") (name "Net-(D10-Pad5)") (class "Default")
      (node (ref "D10") (pin "5") (pinfunction "5_5") (pintype "passive"))
      (node (ref "D12") (pin "28") (pinfunction "28_28") (pintype "passive"))
    )
    (net (code "48") (name "Net-(D10-Pad6)") (class "Default")
      (node (ref "D10") (pin "6") (pinfunction "6_6") (pintype "passive"))
      (node (ref "R7") (pin "2") (pinfunction "2_2") (pintype "passive"))
      (node (ref "R8") (pin "1") (pinfunction "1_1") (pintype "passive"))
    )
    (net (code "49") (name "Net-(D10-Pad8)") (class "Default")
      (node (ref "D10") (pin "8") (pinfunction "8_8") (pintype "passive"))
      (node (ref "D11") (pin "1") (pinfunction "1_1") (pintype "passive"))
    )
    (net (code "50") (name "Net-(D11-Pad2)") (class "Default")
      (node (ref "D11") (pin "2") (pinfunction "2_2") (pintype "passive"))
      (node (ref "R3") (pin "1") (pinfunction "1_1") (pintype "passive"))
      (node (ref "R4") (pin "2") (pinfunction "2_2") (pintype "passive"))
    )
    (net (code "51") (name "Net-(D12-Pad3)") (class "Default")
      (node (ref "D12") (pin "3") (pinfunction "3_3") (pintype "passive"))
      (node (ref "R9") (pin "2") (pinfunction "2_2") (pintype "passive"))
    )
    (net (code "52") (name "Net-(D12-Pad4)") (class "Default")
      (node (ref "D12") (pin "4") (pinfunction "4_4") (pintype "passive"))
      (node (ref "R6") (pin "2") (pinfunction "2_2") (pintype "passive"))
    )
    (net (code "53") (name "Net-(D12-Pad11)") (class "Default")
      (node (ref "D12") (pin "11") (pinfunction "11_11") (pintype "passive"))
      (node (ref "X3") (pin "3") (pinfunction "3_3") (pintype "passive"))
    )
    (net (code "54") (name "Net-(D12-Pad12)") (class "Default")
      (node (ref "D12") (pin "12") (pinfunction "12_12") (pintype "passive"))
      (node (ref "R24") (pin "1") (pinfunction "1_1") (pintype "passive"))
      (node (ref "VD10") (pin "2") (pinfunction "2_2") (pintype "passive"))
    )
    (net (code "55") (name "Net-(D12-Pad13)") (class "Default")
      (node (ref "D12") (pin "13") (pinfunction "13_13") (pintype "passive"))
      (node (ref "R10") (pin "1") (pinfunction "1_1") (pintype "passive"))
      (node (ref "X3") (pin "4") (pinfunction "4_4") (pintype "passive"))
    )
    (net (code "56") (name "Net-(D12-Pad32)") (class "Default")
      (node (ref "D12") (pin "32") (pinfunction "32_32") (pintype "passive"))
      (node (ref "VD9") (pin "2") (pinfunction "2_2") (pintype "passive"))
    )
    (net (code "57") (name "Net-(D12-Pad33)") (class "Default")
      (node (ref "D12") (pin "33") (pinfunction "33_33") (pintype "passive"))
      (node (ref "R12") (pin "1") (pinfunction "1_1") (pintype "passive"))
    )
    (net (code "58") (name "Net-(D12-Pad37)") (class "Default")
      (node (ref "D12") (pin "37") (pinfunction "37_37") (pintype "passive"))
      (node (ref "D18") (pin "11") (pinfunction "11_11") (pintype "passive"))
    )
    (net (code "59") (name "Net-(D12-Pad38)") (class "Default")
      (node (ref "D12") (pin "38") (pinfunction "38_38") (pintype "passive"))
      (node (ref "D18") (pin "12") (pinfunction "12_12") (pintype "passive"))
    )
    (net (code "60") (name "Net-(D12-Pad39)") (class "Default")
      (node (ref "D12") (pin "39") (pinfunction "39_39") (pintype "passive"))
      (node (ref "D18") (pin "13") (pinfunction "13_13") (pintype "passive"))
    )
    (net (code "61") (name "Net-(D12-Pad40)") (class "Default")
      (node (ref "D12") (pin "40") (pinfunction "40_40") (pintype "passive"))
      (node (ref "D18") (pin "14") (pinfunction "14_14") (pintype "passive"))
    )
    (net (code "62") (name "Net-(D12-Pad41)") (class "Default")
      (node (ref "D12") (pin "41") (pinfunction "41_41") (pintype "passive"))
      (node (ref "D18") (pin "15") (pinfunction "15_15") (pintype "passive"))
      (node (ref "VD11") (pin "1") (pinfunction "1_1") (pintype "passive"))
    )
    (net (code "63") (name "Net-(D13-Pad1)") (class "Default")
      (node (ref "D13") (pin "1") (pinfunction "1_1") (pintype "passive"))
      (node (ref "D13") (pin "2") (pinfunction "2_2") (pintype "passive"))
      (node (ref "R11") (pin "2") (pinfunction "2_2") (pintype "passive"))
      (node (ref "X2") (pin "4") (pinfunction "4_4") (pintype "passive"))
    )
    (net (code "64") (name "Net-(D13-Pad3)") (class "Default")
      (node (ref "D13") (pin "3") (pinfunction "3_3") (pintype "passive"))
      (node (ref "T1") (pin "4") (pinfunction "4_4") (pintype "passive"))
      (node (ref "VD6") (pin "2") (pinfunction "2_2") (pintype "passive"))
    )
    (net (code "65") (name "Net-(D13-Pad7)") (class "Default")
      (node (ref "D13") (pin "7") (pinfunction "7_7") (pintype "passive"))
      (node (ref "VD8") (pin "1") (pinfunction "1_1") (pintype "passive"))
    )
    (net (code "66") (name "Net-(D14-Pad1)") (class "Default")
      (node (ref "D14") (pin "1") (pinfunction "1_1") (pintype "passive"))
      (node (ref "R22") (pin "1") (pinfunction "1_1") (pintype "passive"))
      (node (ref "VD10") (pin "1") (pinfunction "1_1") (pintype "passive"))
    )
    (net (code "67") (name "Net-(D14-Pad2)") (class "Default")
      (node (ref "D14") (pin "2") (pinfunction "2_2") (pintype "passive"))
      (node (ref "R20") (pin "2") (pinfunction "2_2") (pintype "passive"))
      (node (ref "R21") (pin "1") (pinfunction "1_1") (pintype "passive"))
      (node (ref "R22") (pin "2") (pinfunction "2_2") (pintype "passive"))
    )
    (net (code "68") (name "Net-(D14-Pad3)") (class "Default")
      (node (ref "D14") (pin "3") (pinfunction "3_3") (pintype "passive"))
      (node (ref "R18") (pin "2") (pinfunction "2_2") (pintype "passive"))
      (node (ref "R19") (pin "2") (pinfunction "2_2") (pintype "passive"))
    )
    (net (code "69") (name "Net-(D14-Pad6)") (class "Default")
      (node (ref "D14") (pin "6") (pinfunction "6_6") (pintype "passive"))
      (node (ref "R26") (pin "3") (pinfunction "3_3") (pintype "passive"))
    )
    (net (code "70") (name "Net-(D15-Pad2)") (class "Default")
      (node (ref "D15") (pin "2") (pinfunction "2_2") (pintype "passive"))
      (node (ref "D15") (pin "3") (pinfunction "3_3") (pintype "passive"))
      (node (ref "R25") (pin "2") (pinfunction "2_2") (pintype "passive"))
    )
    (net (code "71") (name "Net-(D15-Pad5)") (class "Default")
      (node (ref "D15") (pin "5") (pinfunction "5_5") (pintype "passive"))
      (node (ref "D15") (pin "7") (pinfunction "7_7") (pintype "passive"))
      (node (ref "R28") (pin "2") (pinfunction "2_2") (pintype "passive"))
    )
    (net (code "72") (name "Net-(D16-Pad2)") (class "Default")
      (node (ref "D16") (pin "2") (pinfunction "2_2") (pintype "passive"))
      (node (ref "D16") (pin "3") (pinfunction "3_3") (pintype "passive"))
      (node (ref "R34") (pin "2") (pinfunction "2_2") (pintype "passive"))
    )
    (net (code "73") (name "Net-(D16-Pad5)") (class "Default")
      (node (ref "D16") (pin "5") (pinfunction "5_5") (pintype "passive"))
      (node (ref "D16") (pin "7") (pinfunction "7_7") (pintype "passive"))
      (node (ref "R36") (pin "2") (pinfunction "2_2") (pintype "passive"))
    )
    (net (code "74") (name "Net-(D17-Pad2)") (class "Default")
      (node (ref "D17") (pin "2") (pinfunction "2_2") (pintype "passive"))
      (node (ref "R31") (pin "1") (pinfunction "1_1") (pintype "passive"))
    )
    (net (code "75") (name "Net-(D17-Pad3)") (class "Default")
      (node (ref "D17") (pin "3") (pinfunction "3_3") (pintype "passive"))
      (node (ref "D17") (pin "4") (pinfunction "4_4") (pintype "passive"))
    )
    (net (code "76") (name "Net-(D17-Pad11)") (class "Default")
      (node (ref "D17") (pin "11") (pinfunction "11_11") (pintype "passive"))
      (node (ref "R40") (pin "1") (pinfunction "1_1") (pintype "passive"))
    )
    (net (code "77") (name "Net-(D17-Pad12)") (class "Default")
      (node (ref "D17") (pin "12") (pinfunction "12_12") (pintype "passive"))
      (node (ref "R39") (pin "1") (pinfunction "1_1") (pintype "passive"))
    )
    (net (code "78") (name "Net-(D17-Pad13)") (class "Default")
      (node (ref "D17") (pin "13") (pinfunction "13_13") (pintype "passive"))
      (node (ref "R43") (pin "2") (pinfunction "2_2") (pintype "passive"))
    )
    (net (code "79") (name "Net-(D17-Pad14)") (class "Default")
      (node (ref "D17") (pin "14") (pinfunction "14_14") (pintype "passive"))
      (node (ref "D19") (pin "12") (pinfunction "12_12") (pintype "passive"))
      (node (ref "D19") (pin "2") (pinfunction "2_2") (pintype "passive"))
      (node (ref "D19") (pin "5") (pinfunction "5_5") (pintype "passive"))
      (node (ref "D19") (pin "9") (pinfunction "9_9") (pintype "passive"))
      (node (ref "R14") (pin "1") (pinfunction "1_1") (pintype "passive"))
      (node (ref "VD8") (pin "2") (pinfunction "2_2") (pintype "passive"))
    )
    (net (code "80") (name "Net-(D18-Pad1)") (class "Default")
      (node (ref "D18") (pin "1") (pinfunction "1_1") (pintype "passive"))
      (node (ref "D18") (pin "4") (pinfunction "4_4") (pintype "passive"))
    )
    (net (code "81") (name "Net-(D18-Pad2)") (class "Default")
      (node (ref "D18") (pin "2") (pinfunction "2_2") (pintype "passive"))
      (node (ref "R27") (pin "1") (pinfunction "1_1") (pintype "passive"))
      (node (ref "R32") (pin "1") (pinfunction "1_1") (pintype "passive"))
    )
    (net (code "82") (name "Net-(D18-Pad3)") (class "Default")
      (node (ref "D18") (pin "3") (pinfunction "3_3") (pintype "passive"))
      (node (ref "R32") (pin "2") (pinfunction "2_2") (pintype "passive"))
    )
    (net (code "83") (name "Net-(D18-Pad7)") (class "Default")
      (node (ref "D18") (pin "7") (pinfunction "7_7") (pintype "passive"))
      (node (ref "ZQ3") (pin "1") (pinfunction "1_1") (pintype "passive"))
    )
    (net (code "84") (name "Net-(D18-Pad8)") (class "Default")
      (node (ref "D18") (pin "8") (pinfunction "8_8") (pintype "passive"))
      (node (ref "ZQ3") (pin "2") (pinfunction "2_2") (pintype "passive"))
    )
    (net (code "85") (name "Net-(D18-Pad16)") (class "Default")
      (node (ref "D18") (pin "16") (pinfunction "16_16") (pintype "passive"))
      (node (ref "R41") (pin "1") (pinfunction "1_1") (pintype "passive"))
    )
    (net (code "86") (name "Net-(D19-Pad1)") (class "Default")
      (node (ref "D19") (pin "1") (pinfunction "1_1") (pintype "passive"))
      (node (ref "D7") (pin "1") (pinfunction "1_1") (pintype "passive"))
      (node (ref "D7") (pin "4") (pinfunction "4_4") (pintype "passive"))
    )
    (net (code "87") (name "Net-(D19-Pad3)") (class "Default")
      (node (ref "D19") (pin "3") (pinfunction "3_3") (pintype "passive"))
      (node (ref "R33") (pin "2") (pinfunction "2_2") (pintype "passive"))
    )
    (net (code "88") (name "Net-(D19-Pad4)") (class "Default")
      (node (ref "D19") (pin "4") (pinfunction "4_4") (pintype "passive"))
      (node (ref "D6") (pin "1") (pinfunction "1_1") (pintype "passive"))
      (node (ref "D6") (pin "4") (pinfunction "4_4") (pintype "passive"))
    )
    (net (code "89") (name "Net-(D19-Pad6)") (class "Default")
      (node (ref "D19") (pin "6") (pinfunction "6_6") (pintype "passive"))
      (node (ref "R35") (pin "2") (pinfunction "2_2") (pintype "passive"))
    )
    (net (code "90") (name "Net-(D19-Pad8)") (class "Default")
      (node (ref "D19") (pin "8") (pinfunction "8_8") (pintype "passive"))
      (node (ref "R52") (pin "2") (pinfunction "2_2") (pintype "passive"))
    )
    (net (code "91") (name "Net-(D19-Pad10)") (class "Default")
      (node (ref "D19") (pin "10") (pinfunction "10_10") (pintype "passive"))
      (node (ref "D5") (pin "1") (pinfunction "1_1") (pintype "passive"))
      (node (ref "D5") (pin "4") (pinfunction "4_4") (pintype "passive"))
    )
    (net (code "92") (name "Net-(D19-Pad11)") (class "Default")
      (node (ref "D19") (pin "11") (pinfunction "11_11") (pintype "passive"))
      (node (ref "R47") (pin "1") (pinfunction "1_1") (pintype "passive"))
    )
    (net (code "93") (name "Net-(D19-Pad13)") (class "Default")
      (node (ref "D19") (pin "13") (pinfunction "13_13") (pintype "passive"))
      (node (ref "D4") (pin "1") (pinfunction "1_1") (pintype "passive"))
      (node (ref "D4") (pin "4") (pinfunction "4_4") (pintype "passive"))
    )
    (net (code "94") (name "Net-(D20-Pad2)") (class "Default")
      (node (ref "D20") (pin "2") (pinfunction "2_2") (pintype "passive"))
      (node (ref "D20") (pin "3") (pinfunction "3_3") (pintype "passive"))
      (node (ref "R38") (pin "2") (pinfunction "2_2") (pintype "passive"))
    )
    (net (code "95") (name "Net-(D20-Pad6)") (class "Default")
      (node (ref "D20") (pin "6") (pinfunction "6_6") (pintype "passive"))
      (node (ref "D20") (pin "8") (pinfunction "8_8") (pintype "passive"))
      (node (ref "R46") (pin "1") (pinfunction "1_1") (pintype "passive"))
    )
    (net (code "96") (name "Net-(D21-Pad6)") (class "Default")
      (node (ref "D21") (pin "6") (pinfunction "6_6") (pintype "passive"))
      (node (ref "R55") (pin "1") (pinfunction "1_1") (pintype "passive"))
      (node (ref "R58") (pin "2") (pinfunction "2_2") (pintype "passive"))
    )
    (net (code "97") (name "Net-(D22-Pad2)") (class "Default")
      (node (ref "D22") (pin "2") (pinfunction "2_2") (pintype "passive"))
      (node (ref "D22") (pin "3") (pinfunction "3_3") (pintype "passive"))
      (node (ref "R50") (pin "2") (pinfunction "2_2") (pintype "passive"))
    )
    (net (code "98") (name "Net-(D22-Pad6)") (class "Default")
      (node (ref "D22") (pin "6") (pinfunction "6_6") (pintype "passive"))
      (node (ref "D22") (pin "8") (pinfunction "8_8") (pintype "passive"))
      (node (ref "R54") (pin "1") (pinfunction "1_1") (pintype "passive"))
    )
    (net (code "99") (name "Net-(FU1-Pad1)") (class "Default")
      (node (ref "FU1") (pin "1") (pinfunction "1_1") (pintype "passive"))
      (node (ref "X1") (pin "1") (pinfunction "1_1") (pintype "passive"))
    )
    (net (code "100") (name "Net-(R6-Pad1)") (class "Default")
      (node (ref "R6") (pin "1") (pinfunction "1_1") (pintype "passive"))
      (node (ref "VD1") (pin "1") (pinfunction "1_1") (pintype "passive"))
      (node (ref "VD2") (pin "2") (pinfunction "2_2") (pintype "passive"))
      (node (ref "X4") (pin "3") (pinfunction "3_3") (pintype "passive"))
    )
    (net (code "101") (name "Net-(R9-Pad1)") (class "Default")
      (node (ref "R9") (pin "1") (pinfunction "1_1") (pintype "passive"))
      (node (ref "VD3") (pin "2") (pinfunction "2_2") (pintype "passive"))
      (node (ref "VD4") (pin "1") (pinfunction "1_1") (pintype "passive"))
      (node (ref "X4") (pin "2") (pinfunction "2_2") (pintype "passive"))
    )
    (net (code "102") (name "Net-(R15-Pad1)") (class "Default")
      (node (ref "R15") (pin "1") (pinfunction "1_1") (pintype "passive"))
      (node (ref "VD9") (pin "1") (pinfunction "1_1") (pintype "passive"))
    )
    (net (code "103") (name "Net-(R23-Pad3)") (class "Default")
      (node (ref "R23") (pin "3") (pinfunction "3_3") (pintype "passive"))
      (node (ref "R25") (pin "1") (pinfunction "1_1") (pintype "passive"))
    )
    (net (code "104") (name "Net-(R26-Pad1)") (class "Default")
      (node (ref "R26") (pin "1") (pinfunction "1_1") (pintype "passive"))
      (node (ref "R29") (pin "1") (pinfunction "1_1") (pintype "passive"))
    )
    (net (code "105") (name "Net-(R30-Pad3)") (class "Default")
      (node (ref "R30") (pin "3") (pinfunction "3_3") (pintype "passive"))
      (node (ref "R34") (pin "1") (pinfunction "1_1") (pintype "passive"))
    )
    (net (code "106") (name "Net-(R37-Pad3)") (class "Default")
      (node (ref "R37") (pin "3") (pinfunction "3_3") (pintype "passive"))
      (node (ref "R38") (pin "1") (pinfunction "1_1") (pintype "passive"))
    )
    (net (code "107") (name "Net-(R48-Pad3)") (class "Default")
      (node (ref "R48") (pin "3") (pinfunction "3_3") (pintype "passive"))
      (node (ref "R50") (pin "1") (pinfunction "1_1") (pintype "passive"))
    )
    (net (code "108") (name "Net-(R60-Pad1)") (class "Default")
      (node (ref "R60") (pin "1") (pinfunction "1_1") (pintype "passive"))
      (node (ref "VD11") (pin "2") (pinfunction "2_2") (pintype "passive"))
    )
    (net (code "109") (name "Net-(T1-Pad2)") (class "Default")
      (node (ref "T1") (pin "2") (pinfunction "2_2") (pintype "passive"))
      (node (ref "X1") (pin "2") (pinfunction "2_2") (pintype "passive"))
    )
    (net (code "110") (name "unconnected-(D1-Pad9)") (class "Default")
      (node (ref "D1") (pin "9") (pinfunction "9_9") (pintype "passive"))
    )
    (net (code "111") (name "unconnected-(D2-Pad1)") (class "Default")
      (node (ref "D2") (pin "1") (pinfunction "1_1") (pintype "passive"))
    )
    (net (code "112") (name "unconnected-(D3-Pad1)") (class "Default")
      (node (ref "D3") (pin "1") (pinfunction "1_1") (pintype "passive"))
    )
    (net (code "113") (name "unconnected-(D12-Pad1)") (class "Default")
      (node (ref "D12") (pin "1") (pinfunction "1_1") (pintype "passive"))
    )
    (net (code "114") (name "unconnected-(D12-Pad20)") (class "Default")
      (node (ref "D12") (pin "20") (pinfunction "20_20") (pintype "passive"))
    )
    (net (code "115") (name "unconnected-(D12-Pad21)") (class "Default")
      (node (ref "D12") (pin "21") (pinfunction "21_21") (pintype "passive"))
    )
    (net (code "116") (name "unconnected-(D12-Pad22)") (class "Default")
      (node (ref "D12") (pin "22") (pinfunction "22_22") (pintype "passive"))
    )
    (net (code "117") (name "unconnected-(D12-Pad25)") (class "Default")
      (node (ref "D12") (pin "25") (pinfunction "25_25") (pintype "passive"))
    )
    (net (code "118") (name "unconnected-(D12-Pad26)") (class "Default")
      (node (ref "D12") (pin "26") (pinfunction "26_26") (pintype "passive"))
    )
    (net (code "119") (name "unconnected-(D12-Pad27)") (class "Default")
      (node (ref "D12") (pin "27") (pinfunction "27_27") (pintype "passive"))
    )
    (net (code "120") (name "unconnected-(D12-Pad29)") (class "Default")
      (node (ref "D12") (pin "29") (pinfunction "29_29") (pintype "passive"))
    )
    (net (code "121") (name "unconnected-(D12-Pad30)") (class "Default")
      (node (ref "D12") (pin "30") (pinfunction "30_30") (pintype "passive"))
    )
    (net (code "122") (name "unconnected-(D12-Pad31)") (class "Default")
      (node (ref "D12") (pin "31") (pinfunction "31_31") (pintype "passive"))
    )
    (net (code "123") (name "unconnected-(D12-Pad42)") (class "Default")
      (node (ref "D12") (pin "42") (pinfunction "42_42") (pintype "passive"))
    )
    (net (code "124") (name "unconnected-(D17-Pad1)") (class "Default")
      (node (ref "D17") (pin "1") (pinfunction "1_1") (pintype "passive"))
    )
    (net (code "125") (name "unconnected-(D17-Pad10)") (class "Default")
      (node (ref "D17") (pin "10") (pinfunction "10_10") (pintype "passive"))
    )
    (net (code "126") (name "unconnected-(D17-Pad15)") (class "Default")
      (node (ref "D17") (pin "15") (pinfunction "15_15") (pintype "passive"))
    )
  )
)
